# STM32F429.net
KiCad netlist of a schematic drawn in Altium Designer
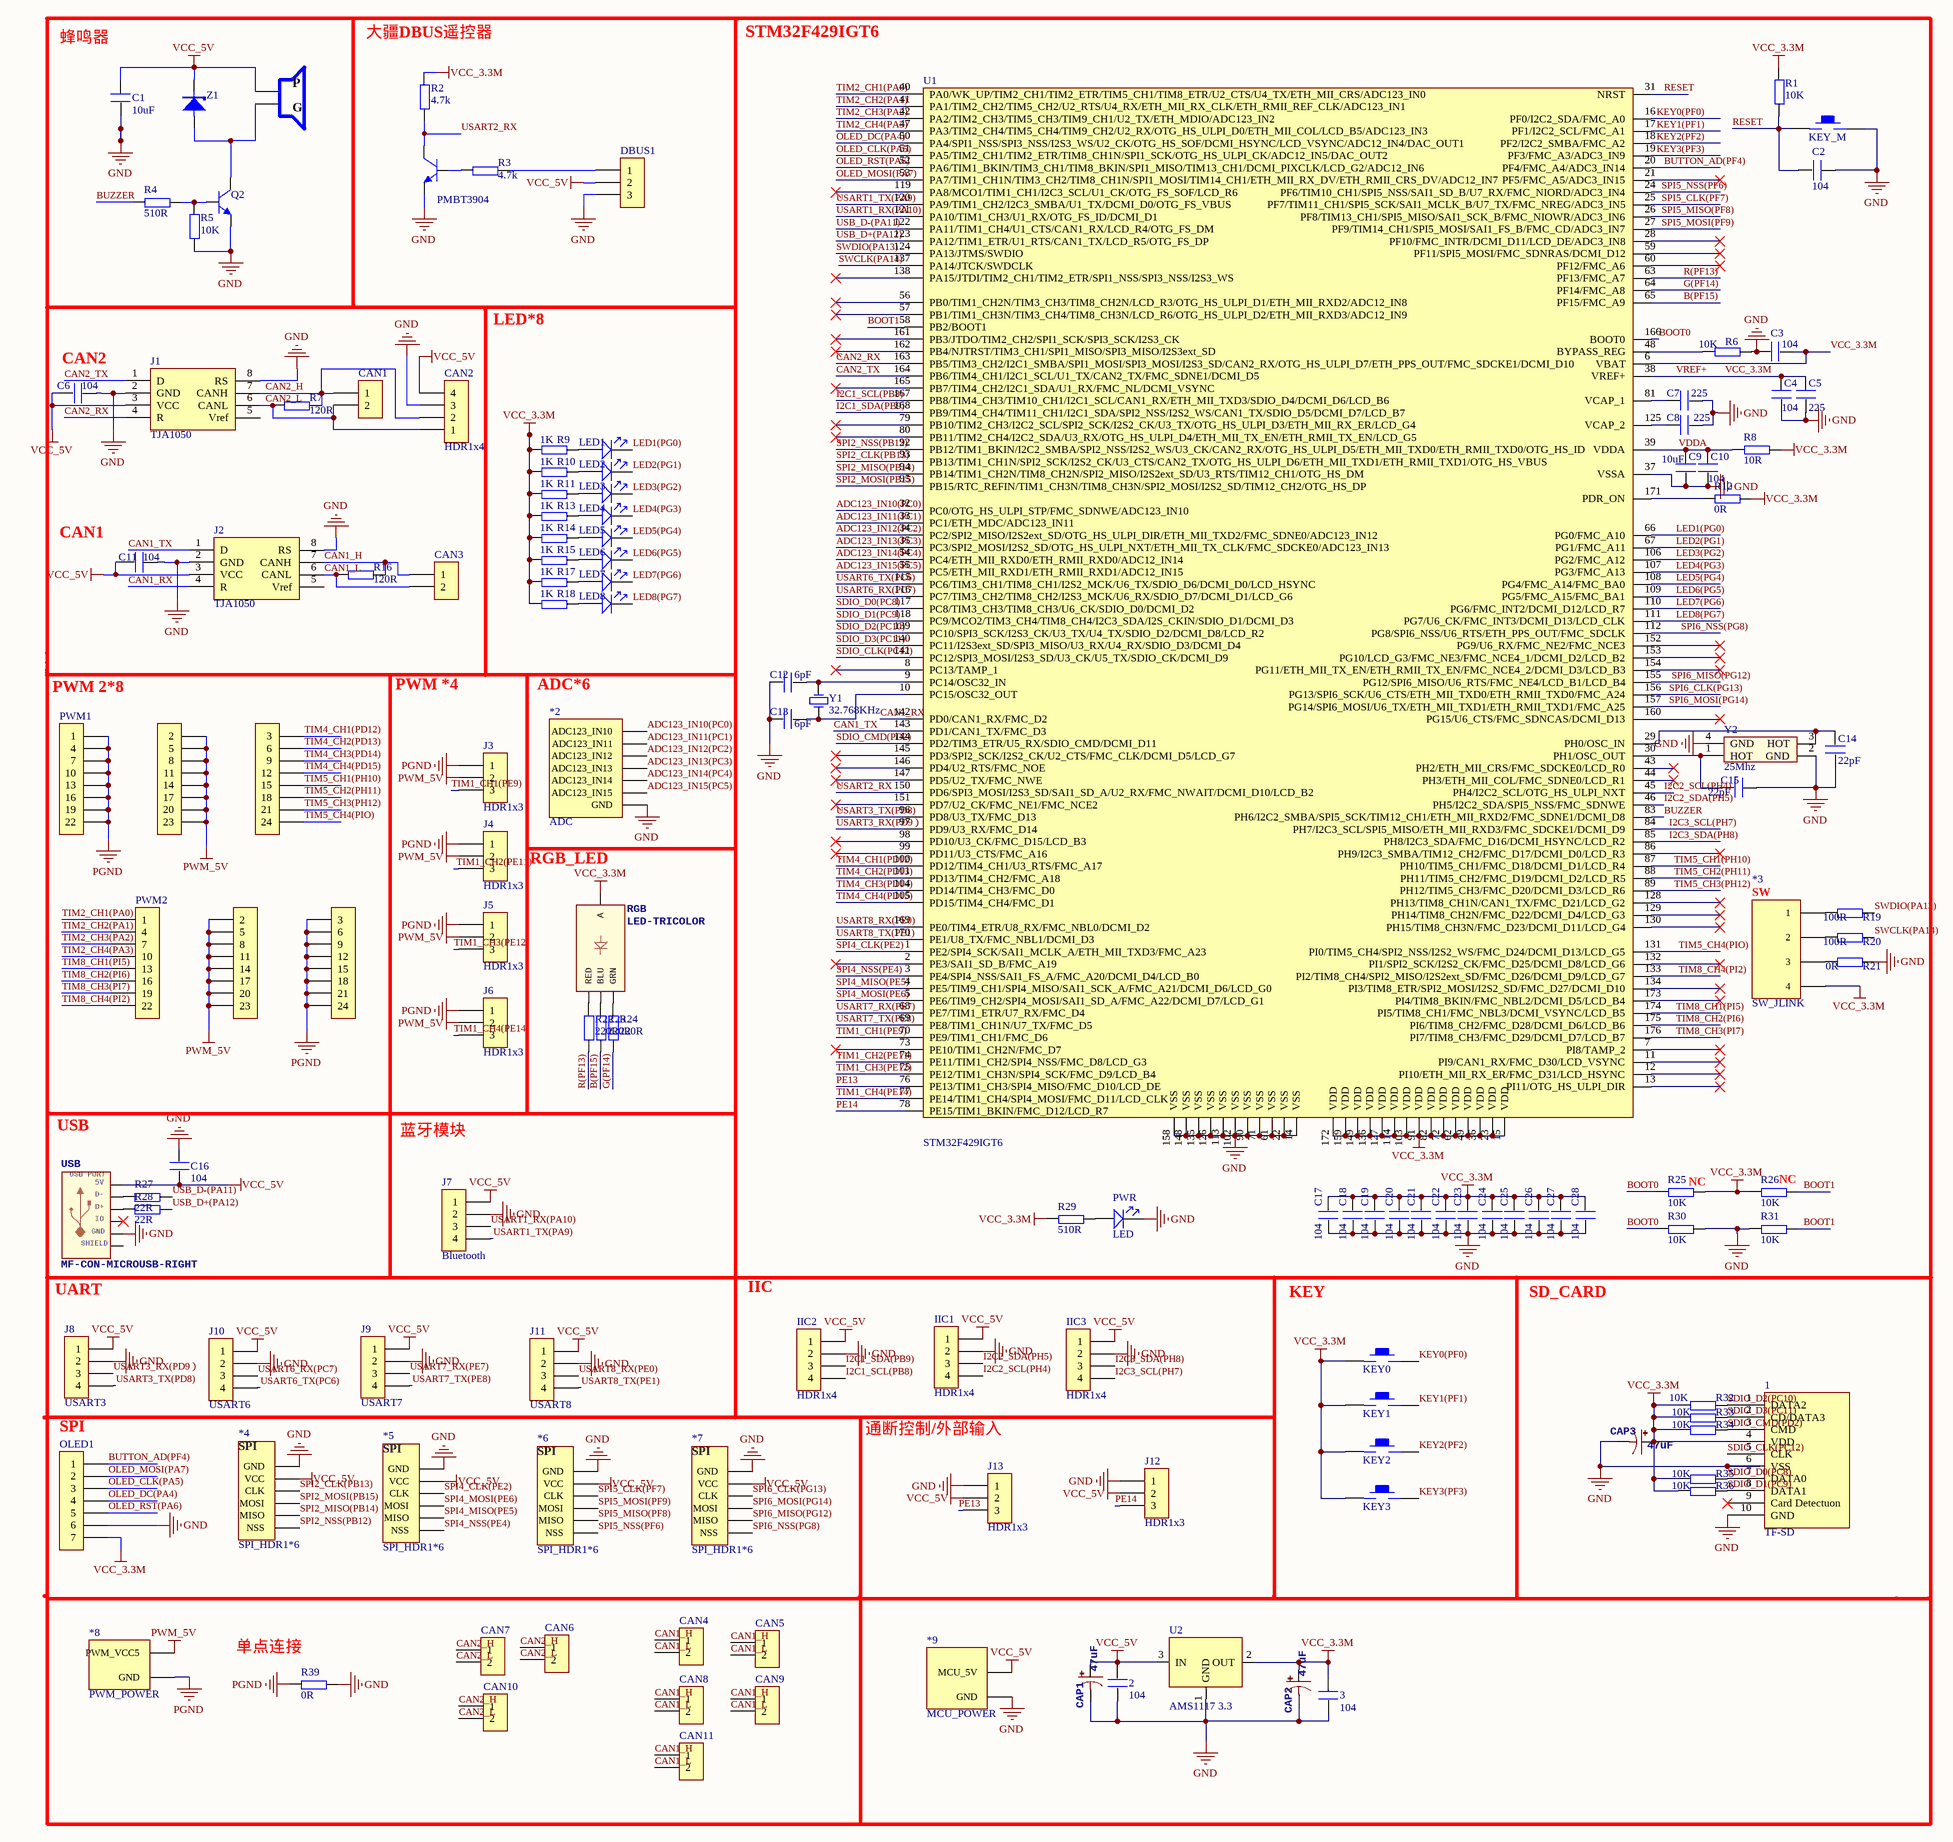
[diagram p0: STM32F429.SchDoc]

(export (version "E")
  (design (tool "Eeschema 10.0.6"))
  (components
    (comp (ref "*1")
      (value "BUZZER")
      (footprint "STM32F429_CORE1:BUZZER")
      (libsource (lib "转接板v2") (part "BUZZER"))
    )
    (comp (ref "*2")
      (value "ADC")
      (footprint "STM32F429_CORE1:ADC")
      (libsource (lib "STM32F429_CORE") (part "ADC"))
    )
    (comp (ref "*3")
      (value "SW_JLINK")
      (footprint "STM32F429_CORE1:GH1.25-立贴-4P")
      (libsource (lib "STM32F429_CORE") (part "SW_JLINK"))
    )
    (comp (ref "*4")
      (value "SPI_HDR1*6")
      (footprint "STM32F429_CORE1:GH1.25-立贴-6P")
      (libsource (lib "STM32F429_CORE") (part "SPI_HDR1*6"))
    )
    (comp (ref "*5")
      (value "SPI_HDR1*6")
      (footprint "STM32F429_CORE1:GH1.25-立贴-6P")
      (libsource (lib "STM32F429_CORE") (part "SPI_HDR1*6"))
    )
    (comp (ref "*6")
      (value "SPI_HDR1*6")
      (footprint "STM32F429_CORE1:GH1.25-立贴-6P")
      (libsource (lib "STM32F429_CORE") (part "SPI_HDR1*6"))
    )
    (comp (ref "*7")
      (value "SPI_HDR1*6")
      (footprint "STM32F429_CORE1:GH1.25-立贴-6P")
      (libsource (lib "STM32F429_CORE") (part "SPI_HDR1*6"))
    )
    (comp (ref "*8")
      (value "PWM_POWER")
      (footprint "XT30_PW母头")
      (libsource (lib "STM32F429_CORE") (part "PWM_POWER"))
    )
    (comp (ref "*9")
      (value "MCU_POWER")
      (footprint "STM32F429_CORE1:XT30_PW母头")
      (libsource (lib "STM32F429_CORE") (part "MCU_POWER"))
    )
    (comp (ref "1")
      (value "TF-SD")
      (footprint "STM32F429_CORE1:TF")
      (libsource (lib "STM32F429_CORE") (part "TF-SD"))
    )
    (comp (ref "2")
      (value "104")
      (footprint "STM32F429_CORE1:0603P")
      (libsource (lib "STM32F429_CORE") (part "C"))
    )
    (comp (ref "3")
      (value "104")
      (footprint "STM32F429_CORE1:0603P")
      (libsource (lib "STM32F429_CORE") (part "C"))
    )
    (comp (ref "C1")
      (value "10uF")
      (footprint "STM32F429_CORE1:0603P")
      (libsource (lib "STM32F429_CORE") (part "C"))
    )
    (comp (ref "C2") (value "104") (footprint "0603P") (libsource (lib "STM32F429_CORE") (part "C")))
    (comp (ref "C3") (value "104") (footprint "0603P") (libsource (lib "STM32F429_CORE") (part "C")))
    (comp (ref "C4") (value "104") (footprint "0603P") (libsource (lib "STM32F429_CORE") (part "C")))
    (comp (ref "C5") (value "225") (footprint "0603P") (libsource (lib "STM32F429_CORE") (part "C")))
    (comp (ref "C6")
      (value "104")
      (footprint "STM32F429_CORE1:0603P")
      (libsource (lib "STM32F429_CORE") (part "C"))
    )
    (comp (ref "C7") (value "225") (footprint "0603P") (libsource (lib "STM32F429_CORE") (part "C")))
    (comp (ref "C8") (value "225") (footprint "0603P") (libsource (lib "STM32F429_CORE") (part "C")))
    (comp (ref "C9") (value "10uF") (footprint "0603P") (libsource (lib "STM32F429_CORE") (part "C")))
    (comp (ref "C10") (value "104") (footprint "0603P") (libsource (lib "STM32F429_CORE") (part "C")))
    (comp (ref "C11")
      (value "104")
      (footprint "STM32F429_CORE1:0603P")
      (libsource (lib "STM32F429_CORE") (part "C"))
    )
    (comp (ref "C12") (value "6pF") (footprint "0603P") (libsource (lib "STM32F429_CORE") (part "C")))
    (comp (ref "C13") (value "6pF") (footprint "0603P") (libsource (lib "STM32F429_CORE") (part "C")))
    (comp (ref "C14") (value "22pF") (footprint "0603P") (libsource (lib "STM32F429_CORE") (part "C")))
    (comp (ref "C15") (value "22pF") (footprint "0603P") (libsource (lib "STM32F429_CORE") (part "C")))
    (comp (ref "C16") (value "104") (footprint "0603P") (libsource (lib "STM32F429_CORE") (part "C")))
    (comp (ref "C17") (value "104") (footprint "0603P") (libsource (lib "STM32F429_CORE") (part "C")))
    (comp (ref "C18") (value "104") (footprint "0603P") (libsource (lib "STM32F429_CORE") (part "C")))
    (comp (ref "C19") (value "104") (footprint "0603P") (libsource (lib "STM32F429_CORE") (part "C")))
    (comp (ref "C20") (value "104") (footprint "0603P") (libsource (lib "STM32F429_CORE") (part "C")))
    (comp (ref "C21") (value "104") (footprint "0603P") (libsource (lib "STM32F429_CORE") (part "C")))
    (comp (ref "C22") (value "104") (footprint "0603P") (libsource (lib "STM32F429_CORE") (part "C")))
    (comp (ref "C23") (value "104") (footprint "0603P") (libsource (lib "STM32F429_CORE") (part "C")))
    (comp (ref "C24") (value "104") (footprint "0603P") (libsource (lib "STM32F429_CORE") (part "C")))
    (comp (ref "C25") (value "104") (footprint "0603P") (libsource (lib "STM32F429_CORE") (part "C")))
    (comp (ref "C26") (value "104") (footprint "0603P") (libsource (lib "STM32F429_CORE") (part "C")))
    (comp (ref "C27") (value "104") (footprint "0603P") (libsource (lib "STM32F429_CORE") (part "C")))
    (comp (ref "C28") (value "104") (footprint "0603P") (libsource (lib "STM32F429_CORE") (part "C")))
    (comp (ref "CAN1")
      (value "HDR1x2-right")
      (footprint "STM32F429_CORE1:GH1.25-立贴-2P")
      (description "Connector")
      (libsource (lib "adaptor_plate") (part "HDR1x2-right"))
    )
    (comp (ref "CAN2")
      (value "HDR1x4")
      (footprint "STM32F429_CORE1:GH1.25-立贴-4P")
      (description "Connector")
      (libsource (lib "") (part "HDR1x4_1"))
    )
    (comp (ref "CAN3")
      (value "HDR1x2-right")
      (footprint "STM32F429_CORE1:GH1.25-立贴-2P")
      (description "Connector")
      (libsource (lib "adaptor_plate") (part "HDR1x2-right"))
    )
    (comp (ref "CAN4")
      (value "HDR1x2-right")
      (footprint "STM32F429_CORE1:GH1.25-立贴-2P")
      (description "Connector")
      (libsource (lib "adaptor_plate") (part "HDR1x2-right"))
    )
    (comp (ref "CAN5")
      (value "HDR1x2-right")
      (footprint "STM32F429_CORE1:GH1.25-立贴-2P")
      (description "Connector")
      (libsource (lib "adaptor_plate") (part "HDR1x2-right"))
    )
    (comp (ref "CAN6")
      (value "HDR1x2-right")
      (footprint "STM32F429_CORE1:GH1.25-立贴-2P")
      (description "Connector")
      (libsource (lib "adaptor_plate") (part "HDR1x2-right"))
    )
    (comp (ref "CAN7")
      (value "HDR1x2-right")
      (footprint "STM32F429_CORE1:GH1.25-立贴-2P")
      (description "Connector")
      (libsource (lib "adaptor_plate") (part "HDR1x2-right"))
    )
    (comp (ref "CAN8")
      (value "HDR1x2-right")
      (footprint "STM32F429_CORE1:GH1.25-立贴-2P")
      (description "Connector")
      (libsource (lib "adaptor_plate") (part "HDR1x2-right"))
    )
    (comp (ref "CAN9")
      (value "HDR1x2-right")
      (footprint "STM32F429_CORE1:GH1.25-立贴-2P")
      (description "Connector")
      (libsource (lib "adaptor_plate") (part "HDR1x2-right"))
    )
    (comp (ref "CAN10")
      (value "HDR1x2-right")
      (footprint "STM32F429_CORE1:GH1.25-立贴-2P")
      (description "Connector")
      (libsource (lib "adaptor_plate") (part "HDR1x2-right"))
    )
    (comp (ref "CAN11")
      (value "HDR1x2-right")
      (footprint "STM32F429_CORE1:GH1.25-立贴-2P")
      (description "Connector")
      (libsource (lib "adaptor_plate") (part "HDR1x2-right"))
    )
    (comp (ref "CAP1") (value "47uF") (footprint "EIA3216") (libsource (lib "") (part "CAP_POL1206_1")))
    (comp (ref "CAP2") (value "47uF") (footprint "EIA3216") (libsource (lib "") (part "CAP_POL1206_1")))
    (comp (ref "CAP3")
      (value "47uF")
      (footprint "EIA3216")
      (libsource (lib "STM32F429_CORE") (part "CAP_POL1206"))
    )
    (comp (ref "DBUS1")
      (value "HDR1x3-right")
      (footprint "STM32F429_CORE1:PIN-1*3-2.54")
      (description "Connector")
      (libsource (lib "adaptor_plate") (part "HDR1x3-right"))
    )
    (comp (ref "IIC1")
      (value "HDR1x4")
      (footprint "STM32F429_CORE1:GH1.25-立贴-4P")
      (description "Connector")
      (libsource (lib "STM32F429_CORE") (part "HDR1x4"))
    )
    (comp (ref "IIC2")
      (value "HDR1x4")
      (footprint "STM32F429_CORE1:GH1.25-立贴-4P")
      (description "Connector")
      (libsource (lib "STM32F429_CORE") (part "HDR1x4"))
    )
    (comp (ref "IIC3")
      (value "HDR1x4")
      (footprint "STM32F429_CORE1:GH1.25-立贴-4P")
      (description "Connector")
      (libsource (lib "STM32F429_CORE") (part "HDR1x4"))
    )
    (comp (ref "J1")
      (value "TJA1050")
      (footprint "SOIC-8_150mil")
      (description "CAN芯片")
      (libsource (lib "adaptor_plate") (part "TJA1050"))
    )
    (comp (ref "J2")
      (value "TJA1050")
      (footprint "SOIC-8_150mil")
      (description "CAN芯片")
      (libsource (lib "adaptor_plate") (part "TJA1050"))
    )
    (comp (ref "J3")
      (value "HDR1x3")
      (footprint "STM32F429_CORE1:HDR1X3")
      (description "Connector")
      (libsource (lib "STM32F429_CORE") (part "HDR1x3"))
    )
    (comp (ref "J4")
      (value "HDR1x3")
      (footprint "STM32F429_CORE1:HDR1X3")
      (description "Connector")
      (libsource (lib "STM32F429_CORE") (part "HDR1x3"))
    )
    (comp (ref "J5")
      (value "HDR1x3")
      (footprint "STM32F429_CORE1:HDR1X3")
      (description "Connector")
      (libsource (lib "STM32F429_CORE") (part "HDR1x3"))
    )
    (comp (ref "J6")
      (value "HDR1x3")
      (footprint "STM32F429_CORE1:HDR1X3")
      (description "Connector")
      (libsource (lib "STM32F429_CORE") (part "HDR1x3"))
    )
    (comp (ref "J7")
      (value "Bluetooth")
      (footprint "STM32F429_CORE1:1X04")
      (description "Connector")
      (libsource (lib "STM32F429_CORE") (part "HDR1x4"))
    )
    (comp (ref "J8")
      (value "USART3")
      (footprint "STM32F429_CORE1:GH1.25-立贴-4P")
      (description "Connector")
      (libsource (lib "STM32F429_CORE") (part "HDR1x4"))
    )
    (comp (ref "J9")
      (value "USART7")
      (footprint "STM32F429_CORE1:GH1.25-立贴-4P")
      (description "Connector")
      (libsource (lib "STM32F429_CORE") (part "HDR1x4"))
    )
    (comp (ref "J10")
      (value "USART6")
      (footprint "STM32F429_CORE1:GH1.25-立贴-4P")
      (description "Connector")
      (libsource (lib "STM32F429_CORE") (part "HDR1x4"))
    )
    (comp (ref "J11")
      (value "USART8")
      (footprint "STM32F429_CORE1:GH1.25-立贴-4P")
      (description "Connector")
      (libsource (lib "STM32F429_CORE") (part "HDR1x4"))
    )
    (comp (ref "J12")
      (value "HDR1x3")
      (footprint "STM32F429_CORE1:HDR1X3")
      (description "Connector")
      (libsource (lib "STM32F429_CORE") (part "HDR1x3"))
    )
    (comp (ref "J13")
      (value "HDR1x3")
      (footprint "STM32F429_CORE1:HDR1X3")
      (description "Connector")
      (libsource (lib "STM32F429_CORE") (part "HDR1x3"))
    )
    (comp (ref "KEY1")
      (value "KEY0")
      (footprint "STM32F429_CORE1:KEY_SOP324225")
      (libsource (lib "STM32F429_CORE") (part "KEY_M"))
    )
    (comp (ref "KEY2")
      (value "KEY1")
      (footprint "STM32F429_CORE1:KEY_SOP324225")
      (libsource (lib "STM32F429_CORE") (part "KEY_M"))
    )
    (comp (ref "KEY3")
      (value "KEY2")
      (footprint "STM32F429_CORE1:KEY_SOP324225")
      (libsource (lib "STM32F429_CORE") (part "KEY_M"))
    )
    (comp (ref "KEY4")
      (value "KEY3")
      (footprint "STM32F429_CORE1:KEY_SOP324225")
      (libsource (lib "STM32F429_CORE") (part "KEY_M"))
    )
    (comp (ref "LED1")
      (value "LED")
      (footprint "STM32F429_CORE1:0805 LED")
      (libsource (lib "STM32F429_CORE") (part "LED"))
    )
    (comp (ref "LED2")
      (value "LED")
      (footprint "STM32F429_CORE1:0805 LED")
      (libsource (lib "STM32F429_CORE") (part "LED"))
    )
    (comp (ref "LED3")
      (value "LED")
      (footprint "STM32F429_CORE1:0805 LED")
      (libsource (lib "STM32F429_CORE") (part "LED"))
    )
    (comp (ref "LED4")
      (value "LED")
      (footprint "STM32F429_CORE1:0805 LED")
      (libsource (lib "STM32F429_CORE") (part "LED"))
    )
    (comp (ref "LED5")
      (value "LED")
      (footprint "STM32F429_CORE1:0805 LED")
      (libsource (lib "STM32F429_CORE") (part "LED"))
    )
    (comp (ref "LED6")
      (value "LED")
      (footprint "STM32F429_CORE1:0805 LED")
      (libsource (lib "STM32F429_CORE") (part "LED"))
    )
    (comp (ref "LED7")
      (value "LED")
      (footprint "STM32F429_CORE1:0805 LED")
      (libsource (lib "STM32F429_CORE") (part "LED"))
    )
    (comp (ref "LED8")
      (value "LED")
      (footprint "STM32F429_CORE1:0805 LED")
      (libsource (lib "STM32F429_CORE") (part "LED"))
    )
    (comp (ref "OLED1")
      (value "HDR1x7-left")
      (footprint "STM32F429_CORE1:GH1.25-立贴-7P")
      (description "Connector")
      (libsource (lib "adaptor_plate") (part "HDR1x7-left"))
    )
    (comp (ref "PWM1")
      (value "HDR3*8-right")
      (footprint "STM32F429_CORE1:PIN-3*8-2.54 - duplicate")
      (description "Connector")
      (libsource (lib "adaptor_plate") (part "HDR3*8-right"))
    )
    (comp (ref "PWM2")
      (value "HDR3*8-left")
      (footprint "STM32F429_CORE1:PIN-3*8-2.54 - duplicate")
      (description "Connector")
      (libsource (lib "adaptor_plate") (part "HDR3*8-left"))
    )
    (comp (ref "PWR")
      (value "LED")
      (footprint "STM32F429_CORE1:0805 LED")
      (libsource (lib "STM32F429_CORE") (part "LED"))
    )
    (comp (ref "Q1")
      (value "PMBT3904")
      (footprint "SOT-23-3")
      (description "NPN Bipolar Transistor")
      (libsource (lib "adaptor_plate") (part "PMBT3904"))
    )
    (comp (ref "Q2")
      (value "S8050")
      (footprint "STM32F429_CORE1:SOT-23-3")
      (description "NPN Bipolar Transistor")
      (libsource (lib "转接板v2") (part "BJT"))
    )
    (comp (ref "R1") (value "10K") (footprint "0603P") (libsource (lib "STM32F429_CORE") (part "R")))
    (comp (ref "R2")
      (value "4.7k")
      (footprint "STM32F429_CORE1:0603P")
      (description "Resistance")
      (libsource (lib "adaptor_plate") (part "RES"))
    )
    (comp (ref "R3")
      (value "4.7k")
      (footprint "STM32F429_CORE1:0603P")
      (description "Resistance")
      (libsource (lib "adaptor_plate") (part "RES"))
    )
    (comp (ref "R4")
      (value "510R")
      (footprint "STM32F429_CORE1:0603P")
      (description "Resistance")
      (libsource (lib "转接板v2") (part "RES"))
    )
    (comp (ref "R5")
      (value "10K")
      (footprint "STM32F429_CORE1:0603P")
      (description "Resistance")
      (libsource (lib "转接板v2") (part "RES"))
    )
    (comp (ref "R6") (value "10K") (footprint "0603P") (libsource (lib "STM32F429_CORE") (part "R")))
    (comp (ref "R7")
      (value "120R")
      (footprint "STM32F429_CORE1:0603P")
      (description "Resistance")
      (libsource (lib "adaptor_plate") (part "RES"))
    )
    (comp (ref "R8") (value "10R") (footprint "0603P") (libsource (lib "STM32F429_CORE") (part "R")))
    (comp (ref "R9") (value "1K") (footprint "0603P") (libsource (lib "STM32F429_CORE") (part "R")))
    (comp (ref "R10") (value "1K") (footprint "0603P") (libsource (lib "STM32F429_CORE") (part "R")))
    (comp (ref "R11") (value "1K") (footprint "0603P") (libsource (lib "STM32F429_CORE") (part "R")))
    (comp (ref "R12") (value "0R") (footprint "0603P") (libsource (lib "STM32F429_CORE") (part "R")))
    (comp (ref "R13") (value "1K") (footprint "0603P") (libsource (lib "STM32F429_CORE") (part "R")))
    (comp (ref "R14") (value "1K") (footprint "0603P") (libsource (lib "STM32F429_CORE") (part "R")))
    (comp (ref "R15") (value "1K") (footprint "0603P") (libsource (lib "STM32F429_CORE") (part "R")))
    (comp (ref "R16")
      (value "120R")
      (footprint "STM32F429_CORE1:0603P")
      (description "Resistance")
      (libsource (lib "adaptor_plate") (part "RES"))
    )
    (comp (ref "R17") (value "1K") (footprint "0603P") (libsource (lib "STM32F429_CORE") (part "R")))
    (comp (ref "R18") (value "1K") (footprint "0603P") (libsource (lib "STM32F429_CORE") (part "R")))
    (comp (ref "R19") (value "100R") (footprint "0603P") (libsource (lib "STM32F429_CORE") (part "R")))
    (comp (ref "R20") (value "100R") (footprint "0603P") (libsource (lib "STM32F429_CORE") (part "R")))
    (comp (ref "R21") (value "0R") (footprint "0603P") (libsource (lib "STM32F429_CORE") (part "R")))
    (comp (ref "R22") (value "220R") (footprint "0603P") (libsource (lib "STM32F429_CORE") (part "R")))
    (comp (ref "R23") (value "220R") (footprint "0603P") (libsource (lib "STM32F429_CORE") (part "R")))
    (comp (ref "R24") (value "220R") (footprint "0603P") (libsource (lib "STM32F429_CORE") (part "R")))
    (comp (ref "R25") (value "10K") (footprint "0603P") (libsource (lib "STM32F429_CORE") (part "R")))
    (comp (ref "R26") (value "10K") (footprint "0603P") (libsource (lib "STM32F429_CORE") (part "R")))
    (comp (ref "R27") (value "22R") (footprint "0603P") (libsource (lib "STM32F429_CORE") (part "R")))
    (comp (ref "R28") (value "22R") (footprint "0603P") (libsource (lib "STM32F429_CORE") (part "R")))
    (comp (ref "R29") (value "510R") (footprint "0603P") (libsource (lib "STM32F429_CORE") (part "R")))
    (comp (ref "R30") (value "10K") (footprint "0603P") (libsource (lib "STM32F429_CORE") (part "R")))
    (comp (ref "R31") (value "10K") (footprint "0603P") (libsource (lib "STM32F429_CORE") (part "R")))
    (comp (ref "R32") (value "10K") (footprint "0603P") (libsource (lib "STM32F429_CORE") (part "R")))
    (comp (ref "R33") (value "10K") (footprint "0603P") (libsource (lib "STM32F429_CORE") (part "R")))
    (comp (ref "R34") (value "10K") (footprint "0603P") (libsource (lib "STM32F429_CORE") (part "R")))
    (comp (ref "R35") (value "10K") (footprint "0603P") (libsource (lib "STM32F429_CORE") (part "R")))
    (comp (ref "R36") (value "10K") (footprint "0603P") (libsource (lib "STM32F429_CORE") (part "R")))
    (comp (ref "R39") (value "0R") (footprint "0805") (libsource (lib "STM32F429_CORE") (part "R")))
    (comp (ref "RGB")
      (value "LED-TRICOLOR")
      (footprint "rgb")
      (libsource (lib "STM32F429_CORE") (part "LED-TRICOLOR"))
    )
    (comp (ref "RST1")
      (value "KEY_M")
      (footprint "STM32F429_CORE1:KEY_SOP324225")
      (libsource (lib "STM32F429_CORE") (part "KEY_M"))
    )
    (comp (ref "U1")
      (value "STM32F429IGT6")
      (footprint "LQFP176")
      (libsource (lib "STM32F429_CORE") (part "STM32F429IGT6"))
    )
    (comp (ref "U2")
      (value "AMS1117 3.3")
      (footprint "SOT_223")
      (libsource (lib "STM32F429_CORE") (part "AMS1117"))
    )
    (comp (ref "USB")
      (value "MF-CON-MICROUSB-RIGHT")
      (footprint "STM32F429_CORE1:micro_usb")
      (fields
        (field (name "USBPORT") "USB PORT")
        (field (name "5V") "5V")
        (field (name "D-") "D-")
        (field (name "D+") "D+")
        (field (name "ID") "ID")
        (field (name "GND") "GND")
        (field (name "SHIELD") "SHIELD")
      )
      (libsource (lib "STM32F429_CORE") (part "USB_MICRO_RIGHT"))
    )
    (comp (ref "Y1")
      (value "32.768KHz")
      (footprint "STM32F429_CORE1:XTAL3215")
      (description "普通晶振")
      (fields (field (name "PUBLISHER") "Altium Limited"))
      (libsource (lib "STM32F429_CORE") (part "XTAL"))
    )
    (comp (ref "Y2")
      (value "25Mhz")
      (footprint "XTAL3225")
      (description "3225贴片无源晶振")
      (libsource (lib "STM32F429_CORE") (part "XTAL_3225"))
    )
    (comp (ref "Z1")
      (value "MMSZ4684")
      (footprint "STM32F429_CORE1:SOD-123")
      (description "Zener Diode")
      (libsource (lib "转接板v2") (part "Diode"))
    )
  )
  (nets
    (net (code "1") (name "/ADC123_IN10(PC0)") (class "Default")
      (node (ref "*2") (pin "0") (pinfunction "ADC123_IN10_0") (pintype "passive"))
      (node (ref "U1") (pin "32") (pinfunction "PC0/OTG_HS_ULPI_STP/FMC_SDNWE/ADC123_IN10_32") (pintype "passive"))
    )
    (net (code "2") (name "/ADC123_IN11(PC1)") (class "Default")
      (node (ref "*2") (pin "1") (pinfunction "ADC123_IN11_1") (pintype "passive"))
      (node (ref "U1") (pin "33") (pinfunction "PC1/ETH_MDC/ADC123_IN11_33") (pintype "passive"))
    )
    (net (code "3") (name "/ADC123_IN12(PC2)") (class "Default")
      (node (ref "*2") (pin "2") (pinfunction "ADC123_IN12_2") (pintype "passive"))
      (node (ref "U1") (pin "34") (pinfunction "PC2/SPI2_MISO/I2S2ext_SD/OTG_HS_ULPI_DIR/ETH_MII_TXD2/FMC_SDNE0/ADC123_IN12_34") (pintype "passive"))
    )
    (net (code "4") (name "/ADC123_IN13(PC3)") (class "Default")
      (node (ref "*2") (pin "3") (pinfunction "ADC123_IN13_3") (pintype "passive"))
      (node (ref "U1") (pin "35") (pinfunction "PC3/SPI2_MOSI/I2S2_SD/OTG_HS_ULPI_NXT/ETH_MII_TX_CLK/FMC_SDCKE0/ADC123_IN13_35") (pintype "passive"))
    )
    (net (code "5") (name "/ADC123_IN14(PC4)") (class "Default")
      (node (ref "*2") (pin "4") (pinfunction "ADC123_IN14_4") (pintype "passive"))
      (node (ref "U1") (pin "54") (pinfunction "PC4/ETH_MII_RXD0/ETH_RMII_RXD0/ADC12_IN14_54") (pintype "passive"))
    )
    (net (code "6") (name "/ADC123_IN15(PC5)") (class "Default")
      (node (ref "*2") (pin "5") (pinfunction "ADC123_IN15_5") (pintype "passive"))
      (node (ref "U1") (pin "55") (pinfunction "PC5/ETH_MII_RXD1/ETH_RMII_RXD1/ADC12_IN15_55") (pintype "passive"))
    )
    (net (code "7") (name "/B(PF15)") (class "Default")
      (node (ref "R23") (pin "1") (pintype "passive"))
      (node (ref "U1") (pin "65") (pinfunction "PF15/FMC_A9_65") (pintype "passive"))
    )
    (net (code "8") (name "/BOOT0") (class "Default")
      (node (ref "R25") (pin "1") (pintype "passive"))
      (node (ref "R30") (pin "1") (pintype "passive"))
      (node (ref "U1") (pin "166") (pinfunction "BOOT0_166") (pintype "passive"))
    )
    (net (code "9") (name "/BOOT1") (class "Default")
      (node (ref "R26") (pin "2") (pintype "passive"))
      (node (ref "R31") (pin "2") (pintype "passive"))
      (node (ref "U1") (pin "58") (pinfunction "PB2/BOOT1_58") (pintype "passive"))
    )
    (net (code "10") (name "/BUTTON_AD(PF4)") (class "Default")
      (node (ref "OLED1") (pin "1") (pinfunction "1_1") (pintype "passive"))
      (node (ref "U1") (pin "20") (pinfunction "PF4/FMC_A4/ADC3_IN14_20") (pintype "passive"))
    )
    (net (code "11") (name "/BUZZER") (class "Default")
      (node (ref "R4") (pin "1") (pintype "passive"))
      (node (ref "U1") (pin "83") (pinfunction "PH6/I2C2_SMBA/SPI5_SCK/TIM12_CH1/ETH_MII_RXD2/FMC_SDNE1/DCMI_D8_83") (pintype "passive"))
    )
    (net (code "12") (name "/CAN1_H") (class "Default")
      (node (ref "CAN11") (pin "1") (pinfunction "1_1") (pintype "passive"))
      (node (ref "CAN3") (pin "1") (pinfunction "1_1") (pintype "passive"))
      (node (ref "CAN4") (pin "1") (pinfunction "1_1") (pintype "passive"))
      (node (ref "CAN5") (pin "1") (pinfunction "1_1") (pintype "passive"))
      (node (ref "CAN8") (pin "1") (pinfunction "1_1") (pintype "passive"))
      (node (ref "CAN9") (pin "1") (pinfunction "1_1") (pintype "passive"))
      (node (ref "J2") (pin "7") (pinfunction "CANH_7") (pintype "passive"))
      (node (ref "R16") (pin "2") (pintype "passive"))
    )
    (net (code "13") (name "/CAN1_L") (class "Default")
      (node (ref "CAN11") (pin "2") (pinfunction "2_2") (pintype "passive"))
      (node (ref "CAN3") (pin "2") (pinfunction "2_2") (pintype "passive"))
      (node (ref "CAN4") (pin "2") (pinfunction "2_2") (pintype "passive"))
      (node (ref "CAN5") (pin "2") (pinfunction "2_2") (pintype "passive"))
      (node (ref "CAN8") (pin "2") (pinfunction "2_2") (pintype "passive"))
      (node (ref "CAN9") (pin "2") (pinfunction "2_2") (pintype "passive"))
      (node (ref "J2") (pin "6") (pinfunction "CANL_6") (pintype "passive"))
      (node (ref "R16") (pin "1") (pintype "passive"))
    )
    (net (code "14") (name "/CAN1_RX") (class "Default")
      (node (ref "J2") (pin "4") (pinfunction "R_4") (pintype "passive"))
      (node (ref "U1") (pin "142") (pinfunction "PD0/CAN1_RX/FMC_D2_142") (pintype "passive"))
    )
    (net (code "15") (name "/CAN1_TX") (class "Default")
      (node (ref "J2") (pin "1") (pinfunction "D_1") (pintype "passive"))
      (node (ref "U1") (pin "143") (pinfunction "PD1/CAN1_TX/FMC_D3_143") (pintype "passive"))
    )
    (net (code "16") (name "/CAN2_H") (class "Default")
      (node (ref "CAN1") (pin "1") (pinfunction "1_1") (pintype "passive"))
      (node (ref "CAN10") (pin "1") (pinfunction "1_1") (pintype "passive"))
      (node (ref "CAN2") (pin "2") (pinfunction "2_2") (pintype "passive"))
      (node (ref "CAN6") (pin "1") (pinfunction "1_1") (pintype "passive"))
      (node (ref "CAN7") (pin "1") (pinfunction "1_1") (pintype "passive"))
      (node (ref "J1") (pin "7") (pinfunction "CANH_7") (pintype "passive"))
      (node (ref "R7") (pin "2") (pintype "passive"))
    )
    (net (code "17") (name "/CAN2_L") (class "Default")
      (node (ref "CAN1") (pin "2") (pinfunction "2_2") (pintype "passive"))
      (node (ref "CAN10") (pin "2") (pinfunction "2_2") (pintype "passive"))
      (node (ref "CAN2") (pin "1") (pinfunction "1_1") (pintype "passive"))
      (node (ref "CAN6") (pin "2") (pinfunction "2_2") (pintype "passive"))
      (node (ref "CAN7") (pin "2") (pinfunction "2_2") (pintype "passive"))
      (node (ref "J1") (pin "6") (pinfunction "CANL_6") (pintype "passive"))
      (node (ref "R7") (pin "1") (pintype "passive"))
    )
    (net (code "18") (name "/CAN2_RX") (class "Default")
      (node (ref "J1") (pin "4") (pinfunction "R_4") (pintype "passive"))
      (node (ref "U1") (pin "163") (pinfunction "PB5/TIM3_CH2/I2C1_SMBA/SPI1_MOSI/SPI3_MOSI/I2S3_SD/CAN2_RX/OTG_HS_ULPI_D7/ETH_PPS_OUT/FMC_SDCKE1/DCMI_D10_163") (pintype "passive"))
    )
    (net (code "19") (name "/CAN2_TX") (class "Default")
      (node (ref "J1") (pin "1") (pinfunction "D_1") (pintype "passive"))
      (node (ref "U1") (pin "164") (pinfunction "PB6/TIM4_CH1/I2C1_SCL/U1_TX/CAN2_TX/FMC_SDNE1/DCMI_D5_164") (pintype "passive"))
    )
    (net (code "20") (name "/G(PF14)") (class "Default")
      (node (ref "R24") (pin "1") (pintype "passive"))
      (node (ref "U1") (pin "64") (pinfunction "PF14/FMC_A8_64") (pintype "passive"))
    )
    (net (code "21") (name "/I2C1_SCL(PB8)") (class "Default")
      (node (ref "IIC2") (pin "4") (pinfunction "4_4") (pintype "passive"))
      (node (ref "U1") (pin "167") (pinfunction "PB8/TIM4_CH3/TIM10_CH1/I2C1_SCL/CAN1_RX/ETH_MII_TXD3/SDIO_D4/DCMI_D6/LCD_B6_167") (pintype "passive"))
    )
    (net (code "22") (name "/I2C1_SDA(PB9)") (class "Default")
      (node (ref "IIC2") (pin "3") (pinfunction "3_3") (pintype "passive"))
      (node (ref "U1") (pin "168") (pinfunction "PB9/TIM4_CH4/TIM11_CH1/I2C1_SDA/SPI2_NSS/I2S2_WS/CAN1_TX/SDIO_D5/DCMI_D7/LCD_B7_168") (pintype "passive"))
    )
    (net (code "23") (name "/I2C2_SCL(PH4)") (class "Default")
      (node (ref "IIC1") (pin "4") (pinfunction "4_4") (pintype "passive"))
      (node (ref "U1") (pin "45") (pinfunction "PH4/I2C2_SCL/OTG_HS_ULPI_NXT_45") (pintype "passive"))
    )
    (net (code "24") (name "/I2C2_SDA(PH5)") (class "Default")
      (node (ref "IIC1") (pin "3") (pinfunction "3_3") (pintype "passive"))
      (node (ref "U1") (pin "46") (pinfunction "PH5/I2C2_SDA/SPI5_NSS/FMC_SDNWE_46") (pintype "passive"))
    )
    (net (code "25") (name "/I2C3_SCL(PH7)") (class "Default")
      (node (ref "IIC3") (pin "4") (pinfunction "4_4") (pintype "passive"))
      (node (ref "U1") (pin "84") (pinfunction "PH7/I2C3_SCL/SPI5_MISO/ETH_MII_RXD3/FMC_SDCKE1/DCMI_D9_84") (pintype "passive"))
    )
    (net (code "26") (name "/I2C3_SDA(PH8)") (class "Default")
      (node (ref "IIC3") (pin "3") (pinfunction "3_3") (pintype "passive"))
      (node (ref "U1") (pin "85") (pinfunction "PH8/I2C3_SDA/FMC_D16/DCMI_HSYNC/LCD_R2_85") (pintype "passive"))
    )
    (net (code "27") (name "/KEY0(PF0)") (class "Default")
      (node (ref "KEY1") (pin "2") (pinfunction "2_2") (pintype "passive"))
      (node (ref "U1") (pin "16") (pinfunction "PF0/I2C2_SDA/FMC_A0_16") (pintype "passive"))
    )
    (net (code "28") (name "/KEY1(PF1)") (class "Default")
      (node (ref "KEY2") (pin "2") (pinfunction "2_2") (pintype "passive"))
      (node (ref "U1") (pin "17") (pinfunction "PF1/I2C2_SCL/FMC_A1_17") (pintype "passive"))
    )
    (net (code "29") (name "/KEY2(PF2)") (class "Default")
      (node (ref "KEY3") (pin "2") (pinfunction "2_2") (pintype "passive"))
      (node (ref "U1") (pin "18") (pinfunction "PF2/I2C2_SMBA/FMC_A2_18") (pintype "passive"))
    )
    (net (code "30") (name "/KEY3(PF3)") (class "Default")
      (node (ref "KEY4") (pin "2") (pinfunction "2_2") (pintype "passive"))
      (node (ref "U1") (pin "19") (pinfunction "PF3/FMC_A3/ADC3_IN9_19") (pintype "passive"))
    )
    (net (code "31") (name "/LED1(PG0)") (class "Default")
      (node (ref "LED1") (pin "2") (pinfunction "2_2") (pintype "passive"))
      (node (ref "U1") (pin "66") (pinfunction "PG0/FMC_A10_66") (pintype "passive"))
    )
    (net (code "32") (name "/LED2(PG1)") (class "Default")
      (node (ref "LED2") (pin "2") (pinfunction "2_2") (pintype "passive"))
      (node (ref "U1") (pin "67") (pinfunction "PG1/FMC_A11_67") (pintype "passive"))
    )
    (net (code "33") (name "/LED3(PG2)") (class "Default")
      (node (ref "LED3") (pin "2") (pinfunction "2_2") (pintype "passive"))
      (node (ref "U1") (pin "106") (pinfunction "PG2/FMC_A12_106") (pintype "passive"))
    )
    (net (code "34") (name "/LED4(PG3)") (class "Default")
      (node (ref "LED4") (pin "2") (pinfunction "2_2") (pintype "passive"))
      (node (ref "U1") (pin "107") (pinfunction "PG3/FMC_A13_107") (pintype "passive"))
    )
    (net (code "35") (name "/LED5(PG4)") (class "Default")
      (node (ref "LED5") (pin "2") (pinfunction "2_2") (pintype "passive"))
      (node (ref "U1") (pin "108") (pinfunction "PG4/FMC_A14/FMC_BA0_108") (pintype "passive"))
    )
    (net (code "36") (name "/LED6(PG5)") (class "Default")
      (node (ref "LED6") (pin "2") (pinfunction "2_2") (pintype "passive"))
      (node (ref "U1") (pin "109") (pinfunction "PG5/FMC_A15/FMC_BA1_109") (pintype "passive"))
    )
    (net (code "37") (name "/LED7(PG6)") (class "Default")
      (node (ref "LED7") (pin "2") (pinfunction "2_2") (pintype "passive"))
      (node (ref "U1") (pin "110") (pinfunction "PG6/FMC_INT2/DCMI_D12/LCD_R7_110") (pintype "passive"))
    )
    (net (code "38") (name "/LED8(PG7)") (class "Default")
      (node (ref "LED8") (pin "2") (pinfunction "2_2") (pintype "passive"))
      (node (ref "U1") (pin "111") (pinfunction "PG7/U6_CK/FMC_INT3/DCMI_D13/LCD_CLK_111") (pintype "passive"))
    )
    (net (code "39") (name "/OLED_CLK(PA5)") (class "Default")
      (node (ref "OLED1") (pin "3") (pinfunction "3_3") (pintype "passive"))
      (node (ref "U1") (pin "51") (pinfunction "PA5/TIM2_CH1/TIM2_ETR/TIM8_CH1N/SPI1_SCK/OTG_HS_ULPI_CK/ADC12_IN5/DAC_OUT2_51") (pintype "passive"))
    )
    (net (code "40") (name "/OLED_DC(PA4)") (class "Default")
      (node (ref "OLED1") (pin "4") (pinfunction "4_4") (pintype "passive"))
      (node (ref "U1") (pin "50") (pinfunction "PA4/SPI1_NSS/SPI3_NSS/I2S3_WS/U2_CK/OTG_HS_SOF/DCMI_HSYNC/LCD_VSYNC/ADC12_IN4/DAC_OUT1_50") (pintype "passive"))
    )
    (net (code "41") (name "/OLED_MOSI(PA7)") (class "Default")
      (node (ref "OLED1") (pin "2") (pinfunction "2_2") (pintype "passive"))
      (node (ref "U1") (pin "53") (pinfunction "PA7/TIM1_CH1N/TIM3_CH2/TIM8_CH1N/SPI1_MOSI/TIM14_CH1/ETH_MII_RX_DV/ETH_RMII_CRS_DV/ADC12_IN7_53") (pintype "passive"))
    )
    (net (code "42") (name "/OLED_RST(PA6)") (class "Default")
      (node (ref "OLED1") (pin "5") (pinfunction "5_5") (pintype "passive"))
      (node (ref "U1") (pin "52") (pinfunction "PA6/TIM1_BKIN/TIM3_CH1/TIM8_BKIN/SPI1_MISO/TIM13_CH1/DCMI_PIXCLK/LCD_G2/ADC12_IN6_52") (pintype "passive"))
    )
    (net (code "43") (name "/PE13") (class "Default")
      (node (ref "J13") (pin "3") (pinfunction "3_3") (pintype "passive"))
      (node (ref "U1") (pin "76") (pinfunction "PE13/TIM1_CH3/SPI4_MISO/FMC_D10/LCD_DE_76") (pintype "passive"))
    )
    (net (code "44") (name "/PE14") (class "Default")
      (node (ref "J12") (pin "3") (pinfunction "3_3") (pintype "passive"))
      (node (ref "U1") (pin "78") (pinfunction "PE15/TIM1_BKIN/FMC_D12/LCD_R7_78") (pintype "passive"))
    )
    (net (code "45") (name "/R(PF13)") (class "Default")
      (node (ref "R22") (pin "1") (pintype "passive"))
      (node (ref "U1") (pin "63") (pinfunction "PF13/FMC_A7_63") (pintype "passive"))
    )
    (net (code "46") (name "/RESET") (class "Default")
      (node (ref "C2") (pin "2") (pintype "passive"))
      (node (ref "R1") (pin "1") (pintype "passive"))
      (node (ref "RST1") (pin "1") (pinfunction "1_1") (pintype "passive"))
      (node (ref "U1") (pin "31") (pinfunction "NRST_31") (pintype "passive"))
    )
    (net (code "47") (name "/SDIO_CLK(PC12)") (class "Default")
      (node (ref "1") (pin "5") (pinfunction "CLK_5") (pintype "passive"))
      (node (ref "U1") (pin "141") (pinfunction "PC12/SPI3_MOSI/I2S3_SD/U3_CK/U5_TX/SDIO_CK/DCMI_D9_141") (pintype "passive"))
    )
    (net (code "48") (name "/SDIO_CMD(PD2)") (class "Default")
      (node (ref "1") (pin "3") (pinfunction "CMD_3") (pintype "passive"))
      (node (ref "R34") (pin "2") (pintype "passive"))
      (node (ref "U1") (pin "144") (pinfunction "PD2/TIM3_ETR/U5_RX/SDIO_CMD/DCMI_D11_144") (pintype "passive"))
    )
    (net (code "49") (name "/SDIO_D0(PC8)") (class "Default")
      (node (ref "1") (pin "7") (pinfunction "DATA0_7") (pintype "passive"))
      (node (ref "R35") (pin "2") (pintype "passive"))
      (node (ref "U1") (pin "117") (pinfunction "PC8/TIM3_CH3/TIM8_CH3/U6_CK/SDIO_D0/DCMI_D2_117") (pintype "passive"))
    )
    (net (code "50") (name "/SDIO_D1(PC9)") (class "Default")
      (node (ref "1") (pin "8") (pinfunction "DATA1_8") (pintype "passive"))
      (node (ref "R36") (pin "2") (pintype "passive"))
      (node (ref "U1") (pin "118") (pinfunction "PC9/MCO2/TIM3_CH4/TIM8_CH4/I2C3_SDA/I2S_CKIN/SDIO_D1/DCMI_D3_118") (pintype "passive"))
    )
    (net (code "51") (name "/SDIO_D2(PC10)") (class "Default")
      (node (ref "1") (pin "1") (pinfunction "DATA2_1") (pintype "passive"))
      (node (ref "R32") (pin "2") (pintype "passive"))
      (node (ref "U1") (pin "139") (pinfunction "PC10/SPI3_SCK/I2S3_CK/U3_TX/U4_TX/SDIO_D2/DCMI_D8/LCD_R2_139") (pintype "passive"))
    )
    (net (code "52") (name "/SDIO_D3(PC11)") (class "Default")
      (node (ref "1") (pin "2") (pinfunction "CD/DATA3_2") (pintype "passive"))
      (node (ref "R33") (pin "2") (pintype "passive"))
      (node (ref "U1") (pin "140") (pinfunction "PC11/I2S3ext_SD/SPI3_MISO/U3_RX/U4_RX/SDIO_D3/DCMI_D4_140") (pintype "passive"))
    )
    (net (code "53") (name "/SPI2_CLK(PB13)") (class "Default")
      (node (ref "*4") (pin "3") (pinfunction "CLK_3") (pintype "passive"))
      (node (ref "U1") (pin "93") (pinfunction "PB13/TIM1_CH1N/SPI2_SCK/I2S2_CK/U3_CTS/CAN2_TX/OTG_HS_ULPI_D6/ETH_MII_TXD1/ETH_RMII_TXD1/OTG_HS_VBUS_93") (pintype "passive"))
    )
    (net (code "54") (name "/SPI2_MISO(PB14)") (class "Default")
      (node (ref "*4") (pin "5") (pinfunction "MISO_5") (pintype "passive"))
      (node (ref "U1") (pin "94") (pinfunction "PB14/TIM1_CH2N/TIM8_CH2N/SPI2_MISO/I2S2ext_SD/U3_RTS/TIM12_CH1/OTG_HS_DM_94") (pintype "passive"))
    )
    (net (code "55") (name "/SPI2_MOSI(PB15)") (class "Default")
      (node (ref "*4") (pin "4") (pinfunction "MOSI_4") (pintype "passive"))
      (node (ref "U1") (pin "95") (pinfunction "PB15/RTC_REFIN/TIM1_CH3N/TIM8_CH3N/SPI2_MOSI/I2S2_SD/TIM12_CH2/OTG_HS_DP_95") (pintype "passive"))
    )
    (net (code "56") (name "/SPI2_NSS(PB12)") (class "Default")
      (node (ref "*4") (pin "6") (pinfunction "NSS_6") (pintype "passive"))
      (node (ref "U1") (pin "92") (pinfunction "PB12/TIM1_BKIN/I2C2_SMBA/SPI2_NSS/I2S2_WS/U3_CK/CAN2_RX/OTG_HS_ULPI_D5/ETH_MII_TXD0/ETH_RMII_TXD0/OTG_HS_ID_92") (pintype "passive"))
    )
    (net (code "57") (name "/SPI4_CLK(PE2)") (class "Default")
      (node (ref "*5") (pin "3") (pinfunction "CLK_3") (pintype "passive"))
      (node (ref "U1") (pin "1") (pinfunction "PE2/SPI4_SCK/SAI1_MCLK_A/ETH_MII_TXD3/FMC_A23_1") (pintype "passive"))
    )
    (net (code "58") (name "/SPI4_MISO(PE5)") (class "Default")
      (node (ref "*5") (pin "5") (pinfunction "MISO_5") (pintype "passive"))
      (node (ref "U1") (pin "4") (pinfunction "PE5/TIM9_CH1/SPI4_MISO/SAI1_SCK_A/FMC_A21/DCMI_D6/LCD_G0_4") (pintype "passive"))
    )
    (net (code "59") (name "/SPI4_MOSI(PE6)") (class "Default")
      (node (ref "*5") (pin "4") (pinfunction "MOSI_4") (pintype "passive"))
      (node (ref "U1") (pin "5") (pinfunction "PE6/TIM9_CH2/SPI4_MOSI/SAI1_SD_A/FMC_A22/DCMI_D7/LCD_G1_5") (pintype "passive"))
    )
    (net (code "60") (name "/SPI4_NSS(PE4)") (class "Default")
      (node (ref "*5") (pin "6") (pinfunction "NSS_6") (pintype "passive"))
      (node (ref "U1") (pin "3") (pinfunction "PE4/SPI4_NSS/SAI1_FS_A/FMC_A20/DCMI_D4/LCD_B0_3") (pintype "passive"))
    )
    (net (code "61") (name "/SPI5_CLK(PF7)") (class "Default")
      (node (ref "*6") (pin "3") (pinfunction "CLK_3") (pintype "passive"))
      (node (ref "U1") (pin "25") (pinfunction "PF7/TIM11_CH1/SPI5_SCK/SAI1_MCLK_B/U7_TX/FMC_NREG/ADC3_IN5_25") (pintype "passive"))
    )
    (net (code "62") (name "/SPI5_MISO(PF8)") (class "Default")
      (node (ref "*6") (pin "5") (pinfunction "MISO_5") (pintype "passive"))
      (node (ref "U1") (pin "26") (pinfunction "PF8/TIM13_CH1/SPI5_MISO/SAI1_SCK_B/FMC_NIOWR/ADC3_IN6_26") (pintype "passive"))
    )
    (net (code "63") (name "/SPI5_MOSI(PF9)") (class "Default")
      (node (ref "*6") (pin "4") (pinfunction "MOSI_4") (pintype "passive"))
      (node (ref "U1") (pin "27") (pinfunction "PF9/TIM14_CH1/SPI5_MOSI/SAI1_FS_B/FMC_CD/ADC3_IN7_27") (pintype "passive"))
    )
    (net (code "64") (name "/SPI5_NSS(PF6)") (class "Default")
      (node (ref "*6") (pin "6") (pinfunction "NSS_6") (pintype "passive"))
      (node (ref "U1") (pin "24") (pinfunction "PF6/TIM10_CH1/SPI5_NSS/SAI1_SD_B/U7_RX/FMC_NIORD/ADC3_IN4_24") (pintype "passive"))
    )
    (net (code "65") (name "/SPI6_CLK(PG13)") (class "Default")
      (node (ref "*7") (pin "3") (pinfunction "CLK_3") (pintype "passive"))
      (node (ref "U1") (pin "156") (pinfunction "PG13/SPI6_SCK/U6_CTS/ETH_MII_TXD0/ETH_RMII_TXD0/FMC_A24_156") (pintype "passive"))
    )
    (net (code "66") (name "/SPI6_MISO(PG12)") (class "Default")
      (node (ref "*7") (pin "5") (pinfunction "MISO_5") (pintype "passive"))
      (node (ref "U1") (pin "155") (pinfunction "PG12/SPI6_MISO/U6_RTS/FMC_NE4/LCD_B1/LCD_B4_155") (pintype "passive"))
    )
    (net (code "67") (name "/SPI6_MOSI(PG14)") (class "Default")
      (node (ref "*7") (pin "4") (pinfunction "MOSI_4") (pintype "passive"))
      (node (ref "U1") (pin "157") (pinfunction "PG14/SPI6_MOSI/U6_TX/ETH_MII_TXD1/ETH_RMII_TXD1/FMC_A25_157") (pintype "passive"))
    )
    (net (code "68") (name "/SPI6_NSS(PG8)") (class "Default")
      (node (ref "*7") (pin "6") (pinfunction "NSS_6") (pintype "passive"))
      (node (ref "U1") (pin "112") (pinfunction "PG8/SPI6_NSS/U6_RTS/ETH_PPS_OUT/FMC_SDCLK_112") (pintype "passive"))
    )
    (net (code "69") (name "/SWCLK(PA14)") (class "Default")
      (node (ref "R20") (pin "2") (pintype "passive"))
      (node (ref "U1") (pin "137") (pinfunction "PA14/JTCK/SWDCLK_137") (pintype "passive"))
    )
    (net (code "70") (name "/SWDIO(PA13)") (class "Default")
      (node (ref "R19") (pin "2") (pintype "passive"))
      (node (ref "U1") (pin "124") (pinfunction "PA13/JTMS/SWDIO_124") (pintype "passive"))
    )
    (net (code "71") (name "/TIM1_CH1(PE9)") (class "Default")
      (node (ref "J3") (pin "3") (pinfunction "3_3") (pintype "passive"))
      (node (ref "U1") (pin "70") (pinfunction "PE9/TIM1_CH1/FMC_D6_70") (pintype "passive"))
    )
    (net (code "72") (name "/TIM1_CH2(PE11)") (class "Default")
      (node (ref "J4") (pin "3") (pinfunction "3_3") (pintype "passive"))
      (node (ref "U1") (pin "74") (pinfunction "PE11/TIM1_CH2/SPI4_NSS/FMC_D8/LCD_G3_74") (pintype "passive"))
    )
    (net (code "73") (name "/TIM1_CH3(PE12)") (class "Default")
      (node (ref "J5") (pin "3") (pinfunction "3_3") (pintype "passive"))
      (node (ref "U1") (pin "75") (pinfunction "PE12/TIM1_CH3N/SPI4_SCK/FMC_D9/LCD_B4_75") (pintype "passive"))
    )
    (net (code "74") (name "/TIM1_CH4(PE14)") (class "Default")
      (node (ref "J6") (pin "3") (pinfunction "3_3") (pintype "passive"))
      (node (ref "U1") (pin "77") (pinfunction "PE14/TIM1_CH4/SPI4_MOSI/FMC_D11/LCD_CLK_77") (pintype "passive"))
    )
    (net (code "75") (name "/TIM2_CH1(PA0)") (class "Default")
      (node (ref "PWM2") (pin "1") (pinfunction "1_1") (pintype "passive"))
      (node (ref "U1") (pin "40") (pinfunction "PA0/WK_UP/TIM2_CH1/TIM2_ETR/TIM5_CH1/TIM8_ETR/U2_CTS/U4_TX/ETH_MII_CRS/ADC123_IN0_40") (pintype "passive"))
    )
    (net (code "76") (name "/TIM2_CH2(PA1)") (class "Default")
      (node (ref "PWM2") (pin "4") (pinfunction "4_4") (pintype "passive"))
      (node (ref "U1") (pin "41") (pinfunction "PA1/TIM2_CH2/TIM5_CH2/U2_RTS/U4_RX/ETH_MII_RX_CLK/ETH_RMII_REF_CLK/ADC123_IN1_41") (pintype "passive"))
    )
    (net (code "77") (name "/TIM2_CH3(PA2)") (class "Default")
      (node (ref "PWM2") (pin "7") (pinfunction "7_7") (pintype "passive"))
      (node (ref "U1") (pin "42") (pinfunction "PA2/TIM2_CH3/TIM5_CH3/TIM9_CH1/U2_TX/ETH_MDIO/ADC123_IN2_42") (pintype "passive"))
    )
    (net (code "78") (name "/TIM2_CH4(PA3)") (class "Default")
      (node (ref "PWM2") (pin "10") (pinfunction "10_10") (pintype "passive"))
      (node (ref "U1") (pin "47") (pinfunction "PA3/TIM2_CH4/TIM5_CH4/TIM9_CH2/U2_RX/OTG_HS_ULPI_D0/ETH_MII_COL/LCD_B5/ADC123_IN3_47") (pintype "passive"))
    )
    (net (code "79") (name "/TIM4_CH1(PD12)") (class "Default")
      (node (ref "PWM1") (pin "3") (pinfunction "3_3") (pintype "passive"))
      (node (ref "U1") (pin "100") (pinfunction "PD12/TIM4_CH1/U3_RTS/FMC_A17_100") (pintype "passive"))
    )
    (net (code "80") (name "/TIM4_CH2(PD13)") (class "Default")
      (node (ref "PWM1") (pin "6") (pinfunction "6_6") (pintype "passive"))
      (node (ref "U1") (pin "101") (pinfunction "PD13/TIM4_CH2/FMC_A18_101") (pintype "passive"))
    )
    (net (code "81") (name "/TIM4_CH3(PD14)") (class "Default")
      (node (ref "PWM1") (pin "9") (pinfunction "9_9") (pintype "passive"))
      (node (ref "U1") (pin "104") (pinfunction "PD14/TIM4_CH3/FMC_D0_104") (pintype "passive"))
    )
    (net (code "82") (name "/TIM4_CH4(PD15)") (class "Default")
      (node (ref "PWM1") (pin "12") (pinfunction "12_12") (pintype "passive"))
      (node (ref "U1") (pin "105") (pinfunction "PD15/TIM4_CH4/FMC_D1_105") (pintype "passive"))
    )
    (net (code "83") (name "/TIM5_CH1(PH10)") (class "Default")
      (node (ref "PWM1") (pin "15") (pinfunction "15_15") (pintype "passive"))
      (node (ref "U1") (pin "87") (pinfunction "PH10/TIM5_CH1/FMC_D18/DCMI_D1/LCD_R4_87") (pintype "passive"))
    )
    (net (code "84") (name "/TIM5_CH2(PH11)") (class "Default")
      (node (ref "PWM1") (pin "18") (pinfunction "18_18") (pintype "passive"))
      (node (ref "U1") (pin "88") (pinfunction "PH11/TIM5_CH2/FMC_D19/DCMI_D2/LCD_R5_88") (pintype "passive"))
    )
    (net (code "85") (name "/TIM5_CH3(PH12)") (class "Default")
      (node (ref "PWM1") (pin "21") (pinfunction "21_21") (pintype "passive"))
      (node (ref "U1") (pin "89") (pinfunction "PH12/TIM5_CH3/FMC_D20/DCMI_D3/LCD_R6_89") (pintype "passive"))
    )
    (net (code "86") (name "/TIM5_CH4(PIO)") (class "Default")
      (node (ref "PWM1") (pin "24") (pinfunction "24_24") (pintype "passive"))
      (node (ref "U1") (pin "131") (pinfunction "PI0/TIM5_CH4/SPI2_NSS/I2S2_WS/FMC_D24/DCMI_D13/LCD_G5_131") (pintype "passive"))
    )
    (net (code "87") (name "/TIM8_CH1(PI5)") (class "Default")
      (node (ref "PWM2") (pin "13") (pinfunction "13_13") (pintype "passive"))
      (node (ref "U1") (pin "174") (pinfunction "PI5/TIM8_CH1/FMC_NBL3/DCMI_VSYNC/LCD_B5_174") (pintype "passive"))
    )
    (net (code "88") (name "/TIM8_CH2(PI6)") (class "Default")
      (node (ref "PWM2") (pin "16") (pinfunction "16_16") (pintype "passive"))
      (node (ref "U1") (pin "175") (pinfunction "PI6/TIM8_CH2/FMC_D28/DCMI_D6/LCD_B6_175") (pintype "passive"))
    )
    (net (code "89") (name "/TIM8_CH3(PI7)") (class "Default")
      (node (ref "PWM2") (pin "19") (pinfunction "19_19") (pintype "passive"))
      (node (ref "U1") (pin "176") (pinfunction "PI7/TIM8_CH3/FMC_D29/DCMI_D7/LCD_B7_176") (pintype "passive"))
    )
    (net (code "90") (name "/TIM8_CH4(PI2)") (class "Default")
      (node (ref "PWM2") (pin "22") (pinfunction "22_22") (pintype "passive"))
      (node (ref "U1") (pin "133") (pinfunction "PI2/TIM8_CH4/SPI2_MISO/I2S2ext_SD/FMC_D26/DCMI_D9/LCD_G7_133") (pintype "passive"))
    )
    (net (code "91") (name "/USART1_RX(PA10)") (class "Default")
      (node (ref "J7") (pin "3") (pinfunction "3_3") (pintype "passive"))
      (node (ref "U1") (pin "121") (pinfunction "PA10/TIM1_CH3/U1_RX/OTG_FS_ID/DCMI_D1_121") (pintype "passive"))
    )
    (net (code "92") (name "/USART1_TX(PA9)") (class "Default")
      (node (ref "J7") (pin "4") (pinfunction "4_4") (pintype "passive"))
      (node (ref "U1") (pin "120") (pinfunction "PA9/TIM1_CH2/I2C3_SMBA/U1_TX/DCMI_D0/OTG_FS_VBUS_120") (pintype "passive"))
    )
    (net (code "93") (name "/USART2_RX") (class "Default")
      (node (ref "Q1") (pin "3") (pinfunction "C_3") (pintype "passive"))
      (node (ref "R2") (pin "1") (pintype "passive"))
      (node (ref "U1") (pin "150") (pinfunction "PD6/SPI3_MOSI/I2S3_SD/SAI1_SD_A/U2_RX/FMC_NWAIT/DCMI_D10/LCD_B2_150") (pintype "passive"))
    )
    (net (code "94") (name "/USART3_RX(PD9）") (class "Default")
      (node (ref "J8") (pin "3") (pinfunction "3_3") (pintype "passive"))
      (node (ref "U1") (pin "97") (pinfunction "PD9/U3_RX/FMC_D14_97") (pintype "passive"))
    )
    (net (code "95") (name "/USART3_TX(PD8)") (class "Default")
      (node (ref "J8") (pin "4") (pinfunction "4_4") (pintype "passive"))
      (node (ref "U1") (pin "96") (pinfunction "PD8/U3_TX/FMC_D13_96") (pintype "passive"))
    )
    (net (code "96") (name "/USART6_RX(PC7)") (class "Default")
      (node (ref "J10") (pin "3") (pinfunction "3_3") (pintype "passive"))
      (node (ref "U1") (pin "116") (pinfunction "PC7/TIM3_CH2/TIM8_CH2/I2S3_MCK/U6_RX/SDIO_D7/DCMI_D1/LCD_G6_116") (pintype "passive"))
    )
    (net (code "97") (name "/USART6_TX(PC6)") (class "Default")
      (node (ref "J10") (pin "4") (pinfunction "4_4") (pintype "passive"))
      (node (ref "U1") (pin "115") (pinfunction "PC6/TIM3_CH1/TIM8_CH1/I2S2_MCK/U6_TX/SDIO_D6/DCMI_D0/LCD_HSYNC_115") (pintype "passive"))
    )
    (net (code "98") (name "/USART7_RX(PE7)") (class "Default")
      (node (ref "J9") (pin "3") (pinfunction "3_3") (pintype "passive"))
      (node (ref "U1") (pin "68") (pinfunction "PE7/TIM1_ETR/U7_RX/FMC_D4_68") (pintype "passive"))
    )
    (net (code "99") (name "/USART7_TX(PE8)") (class "Default")
      (node (ref "J9") (pin "4") (pinfunction "4_4") (pintype "passive"))
      (node (ref "U1") (pin "69") (pinfunction "PE8/TIM1_CH1N/U7_TX/FMC_D5_69") (pintype "passive"))
    )
    (net (code "100") (name "/USART8_RX(PE0)") (class "Default")
      (node (ref "J11") (pin "3") (pinfunction "3_3") (pintype "passive"))
      (node (ref "U1") (pin "169") (pinfunction "PE0/TIM4_ETR/U8_RX/FMC_NBL0/DCMI_D2_169") (pintype "passive"))
    )
    (net (code "101") (name "/USART8_TX(PE1)") (class "Default")
      (node (ref "J11") (pin "4") (pinfunction "4_4") (pintype "passive"))
      (node (ref "U1") (pin "170") (pinfunction "PE1/U8_TX/FMC_NBL1/DCMI_D3_170") (pintype "passive"))
    )
    (net (code "102") (name "/USB_D+(PA12)") (class "Default")
      (node (ref "R28") (pin "2") (pintype "passive"))
      (node (ref "U1") (pin "123") (pinfunction "PA12/TIM1_ETR/U1_RTS/CAN1_TX/LCD_R5/OTG_FS_DP_123") (pintype "passive"))
    )
    (net (code "103") (name "/USB_D-(PA11)") (class "Default")
      (node (ref "R27") (pin "2") (pintype "passive"))
      (node (ref "U1") (pin "122") (pinfunction "PA11/TIM1_CH4/U1_CTS/CAN1_RX/LCD_R4/OTG_FS_DM_122") (pintype "passive"))
    )
    (net (code "104") (name "/VDDA") (class "Default")
      (node (ref "C10") (pin "2") (pintype "passive"))
      (node (ref "C9") (pin "2") (pintype "passive"))
      (node (ref "R8") (pin "1") (pintype "passive"))
      (node (ref "U1") (pin "39") (pinfunction "VDDA_39") (pintype "passive"))
    )
    (net (code "105") (name "GND") (class "Default")
      (node (ref "*2") (pin "6") (pinfunction "GND_6") (pintype "passive"))
      (node (ref "*4") (pin "1") (pinfunction "GND_1") (pintype "passive"))
      (node (ref "*5") (pin "1") (pinfunction "GND_1") (pintype "passive"))
      (node (ref "*6") (pin "1") (pinfunction "GND_1") (pintype "passive"))
      (node (ref "*7") (pin "1") (pinfunction "GND_1") (pintype "passive"))
      (node (ref "*9") (pin "2") (pinfunction "GND_2") (pintype "passive"))
      (node (ref "1") (pin "10") (pinfunction "GND_10") (pintype "passive"))
      (node (ref "1") (pin "6") (pinfunction "VSS_6") (pintype "passive"))
      (node (ref "2") (pin "1") (pintype "passive"))
      (node (ref "3") (pin "1") (pintype "passive"))
      (node (ref "C1") (pin "1") (pintype "passive"))
      (node (ref "C10") (pin "1") (pintype "passive"))
      (node (ref "C11") (pin "1") (pintype "passive"))
      (node (ref "C12") (pin "1") (pintype "passive"))
      (node (ref "C13") (pin "1") (pintype "passive"))
      (node (ref "C14") (pin "1") (pintype "passive"))
      (node (ref "C15") (pin "1") (pintype "passive"))
      (node (ref "C16") (pin "2") (pintype "passive"))
      (node (ref "C17") (pin "1") (pintype "passive"))
      (node (ref "C18") (pin "1") (pintype "passive"))
      (node (ref "C19") (pin "1") (pintype "passive"))
      (node (ref "C2") (pin "1") (pintype "passive"))
      (node (ref "C20") (pin "1") (pintype "passive"))
      (node (ref "C21") (pin "1") (pintype "passive"))
      (node (ref "C22") (pin "1") (pintype "passive"))
      (node (ref "C23") (pin "1") (pintype "passive"))
      (node (ref "C24") (pin "1") (pintype "passive"))
      (node (ref "C25") (pin "1") (pintype "passive"))
      (node (ref "C26") (pin "1") (pintype "passive"))
      (node (ref "C27") (pin "1") (pintype "passive"))
      (node (ref "C28") (pin "1") (pintype "passive"))
      (node (ref "C3") (pin "1") (pintype "passive"))
      (node (ref "C4") (pin "1") (pintype "passive"))
      (node (ref "C5") (pin "1") (pintype "passive"))
      (node (ref "C6") (pin "1") (pintype "passive"))
      (node (ref "C7") (pin "2") (pintype "passive"))
      (node (ref "C8") (pin "2") (pintype "passive"))
      (node (ref "C9") (pin "1") (pintype "passive"))
      (node (ref "CAN2") (pin "3") (pinfunction "3_3") (pintype "passive"))
      (node (ref "CAP1") (pin "C") (pinfunction "-_C") (pintype "passive"))
      (node (ref "CAP2") (pin "C") (pinfunction "-_C") (pintype "passive"))
      (node (ref "CAP3") (pin "C") (pinfunction "-_C") (pintype "passive"))
      (node (ref "DBUS1") (pin "3") (pinfunction "3_3") (pintype "passive"))
      (node (ref "IIC1") (pin "2") (pinfunction "2_2") (pintype "passive"))
      (node (ref "IIC2") (pin "2") (pinfunction "2_2") (pintype "passive"))
      (node (ref "IIC3") (pin "2") (pinfunction "2_2") (pintype "passive"))
      (node (ref "J1") (pin "2") (pinfunction "GND_2") (pintype "passive"))
      (node (ref "J1") (pin "8") (pinfunction "RS_8") (pintype "passive"))
      (node (ref "J10") (pin "2") (pinfunction "2_2") (pintype "passive"))
      (node (ref "J11") (pin "2") (pinfunction "2_2") (pintype "passive"))
      (node (ref "J12") (pin "1") (pinfunction "1_1") (pintype "passive"))
      (node (ref "J13") (pin "1") (pinfunction "1_1") (pintype "passive"))
      (node (ref "J2") (pin "2") (pinfunction "GND_2") (pintype "passive"))
      (node (ref "J2") (pin "8") (pinfunction "RS_8") (pintype "passive"))
      (node (ref "J7") (pin "2") (pinfunction "2_2") (pintype "passive"))
      (node (ref "J8") (pin "2") (pinfunction "2_2") (pintype "passive"))
      (node (ref "J9") (pin "2") (pinfunction "2_2") (pintype "passive"))
      (node (ref "OLED1") (pin "6") (pinfunction "6_6") (pintype "passive"))
      (node (ref "PWR") (pin "2") (pinfunction "2_2") (pintype "passive"))
      (node (ref "Q1") (pin "2") (pinfunction "E_2") (pintype "passive"))
      (node (ref "Q2") (pin "2") (pinfunction "E_2") (pintype "passive"))
      (node (ref "R21") (pin "2") (pintype "passive"))
      (node (ref "R30") (pin "2") (pintype "passive"))
      (node (ref "R31") (pin "1") (pintype "passive"))
      (node (ref "R39") (pin "2") (pintype "passive"))
      (node (ref "R5") (pin "1") (pintype "passive"))
      (node (ref "R6") (pin "2") (pintype "passive"))
      (node (ref "RST1") (pin "2") (pinfunction "2_2") (pintype "passive"))
      (node (ref "U1") (pin "102") (pinfunction "VSS_102") (pintype "passive"))
      (node (ref "U1") (pin "113") (pinfunction "VSS_113") (pintype "passive"))
      (node (ref "U1") (pin "126") (pinfunction "VSS_126") (pintype "passive"))
      (node (ref "U1") (pin "135") (pinfunction "VSS_135") (pintype "passive"))
      (node (ref "U1") (pin "14") (pinfunction "VSS_14") (pintype "passive"))
      (node (ref "U1") (pin "148") (pinfunction "VSS_148") (pintype "passive"))
      (node (ref "U1") (pin "158") (pinfunction "VSS_158") (pintype "passive"))
      (node (ref "U1") (pin "22") (pinfunction "VSS_22") (pintype "passive"))
      (node (ref "U1") (pin "37") (pinfunction "VSSA_37") (pintype "passive"))
      (node (ref "U1") (pin "61") (pinfunction "VSS_61") (pintype "passive"))
      (node (ref "U1") (pin "71") (pinfunction "VSS_71") (pintype "passive"))
      (node (ref "U1") (pin "90") (pinfunction "VSS_90") (pintype "passive"))
      (node (ref "U2") (pin "1") (pinfunction "GND_1") (pintype "passive"))
      (node (ref "USB") (pin "5") (pinfunction "GND_5") (pintype "power_in"))
      (node (ref "Y2") (pin "2") (pinfunction "GND_2") (pintype "passive"))
      (node (ref "Y2") (pin "4") (pinfunction "GND_4") (pintype "passive"))
    )
    (net (code "106") (name "Net-(*3-Pad1)") (class "Default")
      (node (ref "*3") (pin "1") (pinfunction "1_1") (pintype "passive"))
      (node (ref "R19") (pin "1") (pintype "passive"))
    )
    (net (code "107") (name "Net-(*3-Pad2)") (class "Default")
      (node (ref "*3") (pin "2") (pinfunction "2_2") (pintype "passive"))
      (node (ref "R20") (pin "1") (pintype "passive"))
    )
    (net (code "108") (name "Net-(*3-Pad3)") (class "Default")
      (node (ref "*3") (pin "3") (pinfunction "3_3") (pintype "passive"))
      (node (ref "R21") (pin "1") (pintype "passive"))
    )
    (net (code "109") (name "Net-(DBUS1-Pad1)") (class "Default")
      (node (ref "DBUS1") (pin "1") (pinfunction "1_1") (pintype "passive"))
      (node (ref "R3") (pin "2") (pintype "passive"))
    )
    (net (code "110") (name "Net-(LED1-Pad1)") (class "Default")
      (node (ref "LED1") (pin "1") (pinfunction "1_1") (pintype "passive"))
      (node (ref "R9") (pin "2") (pintype "passive"))
    )
    (net (code "111") (name "Net-(LED2-Pad1)") (class "Default")
      (node (ref "LED2") (pin "1") (pinfunction "1_1") (pintype "passive"))
      (node (ref "R10") (pin "2") (pintype "passive"))
    )
    (net (code "112") (name "Net-(LED3-Pad1)") (class "Default")
      (node (ref "LED3") (pin "1") (pinfunction "1_1") (pintype "passive"))
      (node (ref "R11") (pin "2") (pintype "passive"))
    )
    (net (code "113") (name "Net-(LED4-Pad1)") (class "Default")
      (node (ref "LED4") (pin "1") (pinfunction "1_1") (pintype "passive"))
      (node (ref "R13") (pin "2") (pintype "passive"))
    )
    (net (code "114") (name "Net-(LED5-Pad1)") (class "Default")
      (node (ref "LED5") (pin "1") (pinfunction "1_1") (pintype "passive"))
      (node (ref "R14") (pin "2") (pintype "passive"))
    )
    (net (code "115") (name "Net-(LED6-Pad1)") (class "Default")
      (node (ref "LED6") (pin "1") (pinfunction "1_1") (pintype "passive"))
      (node (ref "R15") (pin "2") (pintype "passive"))
    )
    (net (code "116") (name "Net-(LED7-Pad1)") (class "Default")
      (node (ref "LED7") (pin "1") (pinfunction "1_1") (pintype "passive"))
      (node (ref "R17") (pin "2") (pintype "passive"))
    )
    (net (code "117") (name "Net-(LED8-Pad1)") (class "Default")
      (node (ref "LED8") (pin "1") (pinfunction "1_1") (pintype "passive"))
      (node (ref "R18") (pin "2") (pintype "passive"))
    )
    (net (code "118") (name "Net-(PWR-Pad1)") (class "Default")
      (node (ref "PWR") (pin "1") (pinfunction "1_1") (pintype "passive"))
      (node (ref "R29") (pin "2") (pintype "passive"))
    )
    (net (code "119") (name "Net-(Q1-B)") (class "Default")
      (node (ref "Q1") (pin "1") (pinfunction "B_1") (pintype "passive"))
      (node (ref "R3") (pin "1") (pintype "passive"))
    )
    (net (code "120") (name "Net-(Q2-B)") (class "Default")
      (node (ref "Q2") (pin "1") (pinfunction "B_1") (pintype "passive"))
      (node (ref "R4") (pin "2") (pintype "passive"))
      (node (ref "R5") (pin "2") (pintype "passive"))
    )
    (net (code "121") (name "Net-(Q2-C)") (class "Default")
      (node (ref "*1") (pin "2") (pinfunction "2_2") (pintype "passive"))
      (node (ref "Q2") (pin "3") (pinfunction "C_3") (pintype "passive"))
      (node (ref "Z1") (pin "1") (pinfunction "A_1") (pintype "passive"))
    )
    (net (code "122") (name "Net-(RGB-BLU)") (class "Default")
      (node (ref "R23") (pin "2") (pintype "passive"))
      (node (ref "RGB") (pin "B") (pinfunction "BLU_B") (pintype "passive"))
    )
    (net (code "123") (name "Net-(RGB-GRN)") (class "Default")
      (node (ref "R24") (pin "2") (pintype "passive"))
      (node (ref "RGB") (pin "G") (pinfunction "GRN_G") (pintype "passive"))
    )
    (net (code "124") (name "Net-(RGB-RED)") (class "Default")
      (node (ref "R22") (pin "2") (pintype "passive"))
      (node (ref "RGB") (pin "R") (pinfunction "RED_R") (pintype "passive"))
    )
    (net (code "125") (name "Net-(U1-BYPASS_REG)") (class "Default")
      (node (ref "R6") (pin "1") (pintype "passive"))
      (node (ref "U1") (pin "48") (pinfunction "BYPASS_REG_48") (pintype "passive"))
    )
    (net (code "126") (name "Net-(U1-PC14{slash}OSC32_IN)") (class "Default")
      (node (ref "C12") (pin "2") (pintype "passive"))
      (node (ref "U1") (pin "9") (pinfunction "PC14/OSC32_IN_9") (pintype "passive"))
      (node (ref "Y1") (pin "2") (pinfunction "OSC2_2") (pintype "passive"))
    )
    (net (code "127") (name "Net-(U1-PC15{slash}OSC32_OUT)") (class "Default")
      (node (ref "C13") (pin "2") (pintype "passive"))
      (node (ref "U1") (pin "10") (pinfunction "PC15/OSC32_OUT_10") (pintype "passive"))
      (node (ref "Y1") (pin "1") (pinfunction "OSC1_1") (pintype "passive"))
    )
    (net (code "128") (name "Net-(U1-PDR_ON)") (class "Default")
      (node (ref "R12") (pin "1") (pintype "passive"))
      (node (ref "U1") (pin "171") (pinfunction "PDR_ON_171") (pintype "passive"))
    )
    (net (code "129") (name "Net-(U1-PH0{slash}OSC_IN)") (class "Default")
      (node (ref "C14") (pin "2") (pintype "passive"))
      (node (ref "U1") (pin "29") (pinfunction "PH0/OSC_IN_29") (pintype "passive"))
      (node (ref "Y2") (pin "3") (pinfunction "HOT_3") (pintype "passive"))
    )
    (net (code "130") (name "Net-(U1-PH1{slash}OSC_OUT)") (class "Default")
      (node (ref "C15") (pin "2") (pintype "passive"))
      (node (ref "U1") (pin "30") (pinfunction "PH1/OSC_OUT_30") (pintype "passive"))
      (node (ref "Y2") (pin "1") (pinfunction "HOT_1") (pintype "passive"))
    )
    (net (code "131") (name "Net-(U1-VCAP_1)") (class "Default")
      (node (ref "C7") (pin "1") (pintype "passive"))
      (node (ref "U1") (pin "81") (pinfunction "VCAP_1_81") (pintype "passive"))
    )
    (net (code "132") (name "Net-(U1-VCAP_2)") (class "Default")
      (node (ref "C8") (pin "1") (pintype "passive"))
      (node (ref "U1") (pin "125") (pinfunction "VCAP_2_125") (pintype "passive"))
    )
    (net (code "133") (name "Net-(USB-D+)") (class "Default")
      (node (ref "R28") (pin "1") (pintype "passive"))
      (node (ref "USB") (pin "3") (pinfunction "D+_3") (pintype "passive"))
    )
    (net (code "134") (name "Net-(USB-D-)") (class "Default")
      (node (ref "R27") (pin "1") (pintype "passive"))
      (node (ref "USB") (pin "2") (pinfunction "D-_2") (pintype "passive"))
    )
    (net (code "135") (name "PGND") (class "Default")
      (node (ref "*8") (pin "2") (pinfunction "GND_2") (pintype "passive"))
      (node (ref "J3") (pin "1") (pinfunction "1_1") (pintype "passive"))
      (node (ref "J4") (pin "1") (pinfunction "1_1") (pintype "passive"))
      (node (ref "J5") (pin "1") (pinfunction "1_1") (pintype "passive"))
      (node (ref "J6") (pin "1") (pinfunction "1_1") (pintype "passive"))
      (node (ref "PWM1") (pin "1") (pinfunction "1_1") (pintype "passive"))
      (node (ref "PWM1") (pin "10") (pinfunction "10_10") (pintype "passive"))
      (node (ref "PWM1") (pin "13") (pinfunction "13_13") (pintype "passive"))
      (node (ref "PWM1") (pin "16") (pinfunction "16_16") (pintype "passive"))
      (node (ref "PWM1") (pin "19") (pinfunction "19_19") (pintype "passive"))
      (node (ref "PWM1") (pin "22") (pinfunction "22_22") (pintype "passive"))
      (node (ref "PWM1") (pin "4") (pinfunction "4_4") (pintype "passive"))
      (node (ref "PWM1") (pin "7") (pinfunction "7_7") (pintype "passive"))
      (node (ref "PWM2") (pin "12") (pinfunction "12_12") (pintype "passive"))
      (node (ref "PWM2") (pin "15") (pinfunction "15_15") (pintype "passive"))
      (node (ref "PWM2") (pin "18") (pinfunction "18_18") (pintype "passive"))
      (node (ref "PWM2") (pin "21") (pinfunction "21_21") (pintype "passive"))
      (node (ref "PWM2") (pin "24") (pinfunction "24_24") (pintype "passive"))
      (node (ref "PWM2") (pin "3") (pinfunction "3_3") (pintype "passive"))
      (node (ref "PWM2") (pin "6") (pinfunction "6_6") (pintype "passive"))
      (node (ref "PWM2") (pin "9") (pinfunction "9_9") (pintype "passive"))
      (node (ref "R39") (pin "1") (pintype "passive"))
    )
    (net (code "136") (name "PWM_5V") (class "Default")
      (node (ref "*8") (pin "1") (pinfunction "PWM_VCC5_1") (pintype "passive"))
      (node (ref "J3") (pin "2") (pinfunction "2_2") (pintype "passive"))
      (node (ref "J4") (pin "2") (pinfunction "2_2") (pintype "passive"))
      (node (ref "J5") (pin "2") (pinfunction "2_2") (pintype "passive"))
      (node (ref "J6") (pin "2") (pinfunction "2_2") (pintype "passive"))
      (node (ref "PWM1") (pin "11") (pinfunction "11_11") (pintype "passive"))
      (node (ref "PWM1") (pin "14") (pinfunction "14_14") (pintype "passive"))
      (node (ref "PWM1") (pin "17") (pinfunction "17_17") (pintype "passive"))
      (node (ref "PWM1") (pin "2") (pinfunction "2_2") (pintype "passive"))
      (node (ref "PWM1") (pin "20") (pinfunction "20_20") (pintype "passive"))
      (node (ref "PWM1") (pin "23") (pinfunction "23_23") (pintype "passive"))
      (node (ref "PWM1") (pin "5") (pinfunction "5_5") (pintype "passive"))
      (node (ref "PWM1") (pin "8") (pinfunction "8_8") (pintype "passive"))
      (node (ref "PWM2") (pin "11") (pinfunction "11_11") (pintype "passive"))
      (node (ref "PWM2") (pin "14") (pinfunction "14_14") (pintype "passive"))
      (node (ref "PWM2") (pin "17") (pinfunction "17_17") (pintype "passive"))
      (node (ref "PWM2") (pin "2") (pinfunction "2_2") (pintype "passive"))
      (node (ref "PWM2") (pin "20") (pinfunction "20_20") (pintype "passive"))
      (node (ref "PWM2") (pin "23") (pinfunction "23_23") (pintype "passive"))
      (node (ref "PWM2") (pin "5") (pinfunction "5_5") (pintype "passive"))
      (node (ref "PWM2") (pin "8") (pinfunction "8_8") (pintype "passive"))
    )
    (net (code "137") (name "VCC_3.3M") (class "Default")
      (node (ref "*3") (pin "4") (pinfunction "4_4") (pintype "passive"))
      (node (ref "1") (pin "4") (pinfunction "VDD_4") (pintype "passive"))
      (node (ref "3") (pin "2") (pintype "passive"))
      (node (ref "C17") (pin "2") (pintype "passive"))
      (node (ref "C18") (pin "2") (pintype "passive"))
      (node (ref "C19") (pin "2") (pintype "passive"))
      (node (ref "C20") (pin "2") (pintype "passive"))
      (node (ref "C21") (pin "2") (pintype "passive"))
      (node (ref "C22") (pin "2") (pintype "passive"))
      (node (ref "C23") (pin "2") (pintype "passive"))
      (node (ref "C24") (pin "2") (pintype "passive"))
      (node (ref "C25") (pin "2") (pintype "passive"))
      (node (ref "C26") (pin "2") (pintype "passive"))
      (node (ref "C27") (pin "2") (pintype "passive"))
      (node (ref "C28") (pin "2") (pintype "passive"))
      (node (ref "C3") (pin "2") (pintype "passive"))
      (node (ref "C4") (pin "2") (pintype "passive"))
      (node (ref "C5") (pin "2") (pintype "passive"))
      (node (ref "CAP2") (pin "A") (pinfunction "+_A") (pintype "passive"))
      (node (ref "CAP3") (pin "A") (pinfunction "+_A") (pintype "passive"))
      (node (ref "KEY1") (pin "1") (pinfunction "1_1") (pintype "passive"))
      (node (ref "KEY2") (pin "1") (pinfunction "1_1") (pintype "passive"))
      (node (ref "KEY3") (pin "1") (pinfunction "1_1") (pintype "passive"))
      (node (ref "KEY4") (pin "1") (pinfunction "1_1") (pintype "passive"))
      (node (ref "OLED1") (pin "7") (pinfunction "7_7") (pintype "passive"))
      (node (ref "R1") (pin "2") (pintype "passive"))
      (node (ref "R10") (pin "1") (pintype "passive"))
      (node (ref "R11") (pin "1") (pintype "passive"))
      (node (ref "R12") (pin "2") (pintype "passive"))
      (node (ref "R13") (pin "1") (pintype "passive"))
      (node (ref "R14") (pin "1") (pintype "passive"))
      (node (ref "R15") (pin "1") (pintype "passive"))
      (node (ref "R17") (pin "1") (pintype "passive"))
      (node (ref "R18") (pin "1") (pintype "passive"))
      (node (ref "R2") (pin "2") (pintype "passive"))
      (node (ref "R25") (pin "2") (pintype "passive"))
      (node (ref "R26") (pin "1") (pintype "passive"))
      (node (ref "R29") (pin "1") (pintype "passive"))
      (node (ref "R32") (pin "1") (pintype "passive"))
      (node (ref "R33") (pin "1") (pintype "passive"))
      (node (ref "R34") (pin "1") (pintype "passive"))
      (node (ref "R35") (pin "1") (pintype "passive"))
      (node (ref "R36") (pin "1") (pintype "passive"))
      (node (ref "R8") (pin "2") (pintype "passive"))
      (node (ref "R9") (pin "1") (pintype "passive"))
      (node (ref "RGB") (pin "A") (pinfunction "A_A") (pintype "passive"))
      (node (ref "U1") (pin "103") (pinfunction "VDD_103") (pintype "passive"))
      (node (ref "U1") (pin "114") (pinfunction "VDD_114") (pintype "passive"))
      (node (ref "U1") (pin "127") (pinfunction "VDD_127") (pintype "passive"))
      (node (ref "U1") (pin "136") (pinfunction "VDD_136") (pintype "passive"))
      (node (ref "U1") (pin "149") (pinfunction "VDD_149") (pintype "passive"))
      (node (ref "U1") (pin "15") (pinfunction "VDD_15") (pintype "passive"))
      (node (ref "U1") (pin "159") (pinfunction "VDD_159") (pintype "passive"))
      (node (ref "U1") (pin "172") (pinfunction "VDD_172") (pintype "passive"))
      (node (ref "U1") (pin "23") (pinfunction "VDD_23") (pintype "passive"))
      (node (ref "U1") (pin "36") (pinfunction "VDD_36") (pintype "passive"))
      (node (ref "U1") (pin "38") (pinfunction "VREF+_38") (pintype "passive"))
      (node (ref "U1") (pin "49") (pinfunction "VDD_49") (pintype "passive"))
      (node (ref "U1") (pin "6") (pinfunction "VBAT_6") (pintype "passive"))
      (node (ref "U1") (pin "62") (pinfunction "VDD_62") (pintype "passive"))
      (node (ref "U1") (pin "72") (pinfunction "VDD_72") (pintype "passive"))
      (node (ref "U1") (pin "82") (pinfunction "VDD_82") (pintype "passive"))
      (node (ref "U1") (pin "91") (pinfunction "VDD_91") (pintype "passive"))
      (node (ref "U2") (pin "2") (pinfunction "OUT_2") (pintype "passive"))
    )
    (net (code "138") (name "VCC_5V") (class "Default")
      (node (ref "*1") (pin "1") (pinfunction "1_1") (pintype "passive"))
      (node (ref "*4") (pin "2") (pinfunction "VCC_2") (pintype "passive"))
      (node (ref "*5") (pin "2") (pinfunction "VCC_2") (pintype "passive"))
      (node (ref "*6") (pin "2") (pinfunction "VCC_2") (pintype "passive"))
      (node (ref "*7") (pin "2") (pinfunction "VCC_2") (pintype "passive"))
      (node (ref "*9") (pin "1") (pinfunction "MCU_5V_1") (pintype "passive"))
      (node (ref "2") (pin "2") (pintype "passive"))
      (node (ref "C1") (pin "2") (pintype "passive"))
      (node (ref "C11") (pin "2") (pintype "passive"))
      (node (ref "C16") (pin "1") (pintype "passive"))
      (node (ref "C6") (pin "2") (pintype "passive"))
      (node (ref "CAN2") (pin "4") (pinfunction "4_4") (pintype "passive"))
      (node (ref "CAP1") (pin "A") (pinfunction "+_A") (pintype "passive"))
      (node (ref "DBUS1") (pin "2") (pinfunction "2_2") (pintype "passive"))
      (node (ref "IIC1") (pin "1") (pinfunction "1_1") (pintype "passive"))
      (node (ref "IIC2") (pin "1") (pinfunction "1_1") (pintype "passive"))
      (node (ref "IIC3") (pin "1") (pinfunction "1_1") (pintype "passive"))
      (node (ref "J1") (pin "3") (pinfunction "VCC_3") (pintype "passive"))
      (node (ref "J10") (pin "1") (pinfunction "1_1") (pintype "passive"))
      (node (ref "J11") (pin "1") (pinfunction "1_1") (pintype "passive"))
      (node (ref "J12") (pin "2") (pinfunction "2_2") (pintype "passive"))
      (node (ref "J13") (pin "2") (pinfunction "2_2") (pintype "passive"))
      (node (ref "J2") (pin "3") (pinfunction "VCC_3") (pintype "passive"))
      (node (ref "J7") (pin "1") (pinfunction "1_1") (pintype "passive"))
      (node (ref "J8") (pin "1") (pinfunction "1_1") (pintype "passive"))
      (node (ref "J9") (pin "1") (pinfunction "1_1") (pintype "passive"))
      (node (ref "U2") (pin "3") (pinfunction "IN_3") (pintype "passive"))
      (node (ref "USB") (pin "1") (pinfunction "5V_1") (pintype "power_in"))
      (node (ref "Z1") (pin "2") (pinfunction "C_2") (pintype "passive"))
    )
    (net (code "139") (name "unconnected-(1-Card_Detectuon-Pad9)") (class "Default")
      (node (ref "1") (pin "9") (pinfunction "Card_Detectuon_9") (pintype "passive+no_connect"))
    )
    (net (code "140") (name "unconnected-(J1-Vref-Pad5)") (class "Default")
      (node (ref "J1") (pin "5") (pinfunction "Vref_5") (pintype "passive"))
    )
    (net (code "141") (name "unconnected-(J2-Vref-Pad5)") (class "Default")
      (node (ref "J2") (pin "5") (pinfunction "Vref_5") (pintype "passive"))
    )
    (net (code "142") (name "unconnected-(U1-PA8{slash}MCO1{slash}TIM1_CH1{slash}I2C3_SCL{slash}U1_CK{slash}OTG_FS_SOF{slash}LCD_R6-Pad119)") (class "Default")
      (node (ref "U1") (pin "119") (pinfunction "PA8/MCO1/TIM1_CH1/I2C3_SCL/U1_CK/OTG_FS_SOF/LCD_R6_119") (pintype "passive+no_connect"))
    )
    (net (code "143") (name "unconnected-(U1-PA15{slash}JTDI{slash}TIM2_CH1{slash}TIM2_ETR{slash}SPI1_NSS{slash}SPI3_NSS{slash}I2S3_WS-Pad138)") (class "Default")
      (node (ref "U1") (pin "138") (pinfunction "PA15/JTDI/TIM2_CH1/TIM2_ETR/SPI1_NSS/SPI3_NSS/I2S3_WS_138") (pintype "passive+no_connect"))
    )
    (net (code "144") (name "unconnected-(U1-PB0{slash}TIM1_CH2N{slash}TIM3_CH3{slash}TIM8_CH2N{slash}LCD_R3{slash}OTG_HS_ULPI_D1{slash}ETH_MII_RXD2{slash}ADC12_IN8-Pad56)") (class "Default")
      (node (ref "U1") (pin "56") (pinfunction "PB0/TIM1_CH2N/TIM3_CH3/TIM8_CH2N/LCD_R3/OTG_HS_ULPI_D1/ETH_MII_RXD2/ADC12_IN8_56") (pintype "passive+no_connect"))
    )
    (net (code "145") (name "unconnected-(U1-PB1{slash}TIM1_CH3N{slash}TIM3_CH4{slash}TIM8_CH3N{slash}LCD_R6{slash}OTG_HS_ULPI_D2{slash}ETH_MII_RXD3{slash}ADC12_IN9-Pad57)") (class "Default")
      (node (ref "U1") (pin "57") (pinfunction "PB1/TIM1_CH3N/TIM3_CH4/TIM8_CH3N/LCD_R6/OTG_HS_ULPI_D2/ETH_MII_RXD3/ADC12_IN9_57") (pintype "passive+no_connect"))
    )
    (net (code "146") (name "unconnected-(U1-PB3{slash}JTDO{slash}TIM2_CH2{slash}SPI1_SCK{slash}SPI3_SCK{slash}I2S3_CK-Pad161)") (class "Default")
      (node (ref "U1") (pin "161") (pinfunction "PB3/JTDO/TIM2_CH2/SPI1_SCK/SPI3_SCK/I2S3_CK_161") (pintype "passive+no_connect"))
    )
    (net (code "147") (name "unconnected-(U1-PB4{slash}NJTRST{slash}TIM3_CH1{slash}SPI1_MISO{slash}SPI3_MISO{slash}I2S3ext_SD-Pad162)") (class "Default")
      (node (ref "U1") (pin "162") (pinfunction "PB4/NJTRST/TIM3_CH1/SPI1_MISO/SPI3_MISO/I2S3ext_SD_162") (pintype "passive+no_connect"))
    )
    (net (code "148") (name "unconnected-(U1-PB7{slash}TIM4_CH2{slash}I2C1_SDA{slash}U1_RX{slash}FMC_NL{slash}DCMI_VSYNC-Pad165)") (class "Default")
      (node (ref "U1") (pin "165") (pinfunction "PB7/TIM4_CH2/I2C1_SDA/U1_RX/FMC_NL/DCMI_VSYNC_165") (pintype "passive+no_connect"))
    )
    (net (code "149") (name "unconnected-(U1-PB10{slash}TIM2_CH3{slash}I2C2_SCL{slash}SPI2_SCK{slash}I2S2_CK{slash}U3_TX{slash}OTG_HS_ULPI_D3{slash}ETH_MII_RX_ER{slash}LCD_G4-Pad79)") (class "Default")
      (node (ref "U1") (pin "79") (pinfunction "PB10/TIM2_CH3/I2C2_SCL/SPI2_SCK/I2S2_CK/U3_TX/OTG_HS_ULPI_D3/ETH_MII_RX_ER/LCD_G4_79") (pintype "passive+no_connect"))
    )
    (net (code "150") (name "unconnected-(U1-PB11{slash}TIM2_CH4{slash}I2C2_SDA{slash}U3_RX{slash}OTG_HS_ULPI_D4{slash}ETH_MII_TX_EN{slash}ETH_RMII_TX_EN{slash}LCD_G5-Pad80)") (class "Default")
      (node (ref "U1") (pin "80") (pinfunction "PB11/TIM2_CH4/I2C2_SDA/U3_RX/OTG_HS_ULPI_D4/ETH_MII_TX_EN/ETH_RMII_TX_EN/LCD_G5_80") (pintype "passive+no_connect"))
    )
    (net (code "151") (name "unconnected-(U1-PC13{slash}TAMP_1-Pad8)") (class "Default")
      (node (ref "U1") (pin "8") (pinfunction "PC13/TAMP_1_8") (pintype "passive+no_connect"))
    )
    (net (code "152") (name "unconnected-(U1-PD3{slash}SPI2_SCK{slash}I2S2_CK{slash}U2_CTS{slash}FMC_CLK{slash}DCMI_D5{slash}LCD_G7-Pad145)") (class "Default")
      (node (ref "U1") (pin "145") (pinfunction "PD3/SPI2_SCK/I2S2_CK/U2_CTS/FMC_CLK/DCMI_D5/LCD_G7_145") (pintype "passive+no_connect"))
    )
    (net (code "153") (name "unconnected-(U1-PD4{slash}U2_RTS{slash}FMC_NOE-Pad146)") (class "Default")
      (node (ref "U1") (pin "146") (pinfunction "PD4/U2_RTS/FMC_NOE_146") (pintype "passive+no_connect"))
    )
    (net (code "154") (name "unconnected-(U1-PD5{slash}U2_TX{slash}FMC_NWE-Pad147)") (class "Default")
      (node (ref "U1") (pin "147") (pinfunction "PD5/U2_TX/FMC_NWE_147") (pintype "passive+no_connect"))
    )
    (net (code "155") (name "unconnected-(U1-PD7{slash}U2_CK{slash}FMC_NE1{slash}FMC_NCE2-Pad151)") (class "Default")
      (node (ref "U1") (pin "151") (pinfunction "PD7/U2_CK/FMC_NE1/FMC_NCE2_151") (pintype "passive+no_connect"))
    )
    (net (code "156") (name "unconnected-(U1-PD10{slash}U3_CK{slash}FMC_D15{slash}LCD_B3-Pad98)") (class "Default")
      (node (ref "U1") (pin "98") (pinfunction "PD10/U3_CK/FMC_D15/LCD_B3_98") (pintype "passive+no_connect"))
    )
    (net (code "157") (name "unconnected-(U1-PD11{slash}U3_CTS{slash}FMC_A16-Pad99)") (class "Default")
      (node (ref "U1") (pin "99") (pinfunction "PD11/U3_CTS/FMC_A16_99") (pintype "passive+no_connect"))
    )
    (net (code "158") (name "unconnected-(U1-PE3{slash}SAI1_SD_B{slash}FMC_A19-Pad2)") (class "Default")
      (node (ref "U1") (pin "2") (pinfunction "PE3/SAI1_SD_B/FMC_A19_2") (pintype "passive+no_connect"))
    )
    (net (code "159") (name "unconnected-(U1-PE10{slash}TIM1_CH2N{slash}FMC_D7-Pad73)") (class "Default")
      (node (ref "U1") (pin "73") (pinfunction "PE10/TIM1_CH2N/FMC_D7_73") (pintype "passive+no_connect"))
    )
    (net (code "160") (name "unconnected-(U1-PF5{slash}FMC_A5{slash}ADC3_IN15-Pad21)") (class "Default")
      (node (ref "U1") (pin "21") (pinfunction "PF5/FMC_A5/ADC3_IN15_21") (pintype "passive+no_connect"))
    )
    (net (code "161") (name "unconnected-(U1-PF10{slash}FMC_INTR{slash}DCMI_D11{slash}LCD_DE{slash}ADC3_IN8-Pad28)") (class "Default")
      (node (ref "U1") (pin "28") (pinfunction "PF10/FMC_INTR/DCMI_D11/LCD_DE/ADC3_IN8_28") (pintype "passive+no_connect"))
    )
    (net (code "162") (name "unconnected-(U1-PF11{slash}SPI5_MOSI{slash}FMC_SDNRAS{slash}DCMI_D12-Pad59)") (class "Default")
      (node (ref "U1") (pin "59") (pinfunction "PF11/SPI5_MOSI/FMC_SDNRAS/DCMI_D12_59") (pintype "passive+no_connect"))
    )
    (net (code "163") (name "unconnected-(U1-PF12{slash}FMC_A6-Pad60)") (class "Default")
      (node (ref "U1") (pin "60") (pinfunction "PF12/FMC_A6_60") (pintype "passive+no_connect"))
    )
    (net (code "164") (name "unconnected-(U1-PG9{slash}U6_RX{slash}FMC_NE2{slash}FMC_NCE3-Pad152)") (class "Default")
      (node (ref "U1") (pin "152") (pinfunction "PG9/U6_RX/FMC_NE2/FMC_NCE3_152") (pintype "passive+no_connect"))
    )
    (net (code "165") (name "unconnected-(U1-PG10{slash}LCD_G3{slash}FMC_NE3{slash}FMC_NCE4_1{slash}DCMI_D2{slash}LCD_B2-Pad153)") (class "Default")
      (node (ref "U1") (pin "153") (pinfunction "PG10/LCD_G3/FMC_NE3/FMC_NCE4_1/DCMI_D2/LCD_B2_153") (pintype "passive+no_connect"))
    )
    (net (code "166") (name "unconnected-(U1-PG11{slash}ETH_MII_TX_EN{slash}ETH_RMII_TX_EN{slash}FMC_NCE4_2{slash}DCMI_D3{slash}LCD_B3-Pad154)") (class "Default")
      (node (ref "U1") (pin "154") (pinfunction "PG11/ETH_MII_TX_EN/ETH_RMII_TX_EN/FMC_NCE4_2/DCMI_D3/LCD_B3_154") (pintype "passive+no_connect"))
    )
    (net (code "167") (name "unconnected-(U1-PG15{slash}U6_CTS{slash}FMC_SDNCAS{slash}DCMI_D13-Pad160)") (class "Default")
      (node (ref "U1") (pin "160") (pinfunction "PG15/U6_CTS/FMC_SDNCAS/DCMI_D13_160") (pintype "passive+no_connect"))
    )
    (net (code "168") (name "unconnected-(U1-PH2{slash}ETH_MII_CRS{slash}FMC_SDCKE0{slash}LCD_R0-Pad43)") (class "Default")
      (node (ref "U1") (pin "43") (pinfunction "PH2/ETH_MII_CRS/FMC_SDCKE0/LCD_R0_43") (pintype "passive+no_connect"))
    )
    (net (code "169") (name "unconnected-(U1-PH3{slash}ETH_MII_COL{slash}FMC_SDNE0{slash}LCD_R1-Pad44)") (class "Default")
      (node (ref "U1") (pin "44") (pinfunction "PH3/ETH_MII_COL/FMC_SDNE0/LCD_R1_44") (pintype "passive+no_connect"))
    )
    (net (code "170") (name "unconnected-(U1-PH9{slash}I2C3_SMBA{slash}TIM12_CH2{slash}FMC_D17{slash}DCMI_D0{slash}LCD_R3-Pad86)") (class "Default")
      (node (ref "U1") (pin "86") (pinfunction "PH9/I2C3_SMBA/TIM12_CH2/FMC_D17/DCMI_D0/LCD_R3_86") (pintype "passive+no_connect"))
    )
    (net (code "171") (name "unconnected-(U1-PH13{slash}TIM8_CH1N{slash}CAN1_TX{slash}FMC_D21{slash}LCD_G2-Pad128)") (class "Default")
      (node (ref "U1") (pin "128") (pinfunction "PH13/TIM8_CH1N/CAN1_TX/FMC_D21/LCD_G2_128") (pintype "passive+no_connect"))
    )
    (net (code "172") (name "unconnected-(U1-PH14{slash}TIM8_CH2N{slash}FMC_D22{slash}DCMI_D4{slash}LCD_G3-Pad129)") (class "Default")
      (node (ref "U1") (pin "129") (pinfunction "PH14/TIM8_CH2N/FMC_D22/DCMI_D4/LCD_G3_129") (pintype "passive+no_connect"))
    )
    (net (code "173") (name "unconnected-(U1-PH15{slash}TIM8_CH3N{slash}FMC_D23{slash}DCMI_D11{slash}LCD_G4-Pad130)") (class "Default")
      (node (ref "U1") (pin "130") (pinfunction "PH15/TIM8_CH3N/FMC_D23/DCMI_D11/LCD_G4_130") (pintype "passive+no_connect"))
    )
    (net (code "174") (name "unconnected-(U1-PI1{slash}SPI2_SCK{slash}I2S2_CK{slash}FMC_D25{slash}DCMI_D8{slash}LCD_G6-Pad132)") (class "Default")
      (node (ref "U1") (pin "132") (pinfunction "PI1/SPI2_SCK/I2S2_CK/FMC_D25/DCMI_D8/LCD_G6_132") (pintype "passive+no_connect"))
    )
    (net (code "175") (name "unconnected-(U1-PI3{slash}TIM8_ETR{slash}SPI2_MOSI{slash}I2S2_SD{slash}FMC_D27{slash}DCMI_D10-Pad134)") (class "Default")
      (node (ref "U1") (pin "134") (pinfunction "PI3/TIM8_ETR/SPI2_MOSI/I2S2_SD/FMC_D27/DCMI_D10_134") (pintype "passive+no_connect"))
    )
    (net (code "176") (name "unconnected-(U1-PI4{slash}TIM8_BKIN{slash}FMC_NBL2{slash}DCMI_D5{slash}LCD_B4-Pad173)") (class "Default")
      (node (ref "U1") (pin "173") (pinfunction "PI4/TIM8_BKIN/FMC_NBL2/DCMI_D5/LCD_B4_173") (pintype "passive+no_connect"))
    )
    (net (code "177") (name "unconnected-(U1-PI8{slash}TAMP_2-Pad7)") (class "Default")
      (node (ref "U1") (pin "7") (pinfunction "PI8/TAMP_2_7") (pintype "passive+no_connect"))
    )
    (net (code "178") (name "unconnected-(U1-PI9{slash}CAN1_RX{slash}FMC_D30{slash}LCD_VSYNC-Pad11)") (class "Default")
      (node (ref "U1") (pin "11") (pinfunction "PI9/CAN1_RX/FMC_D30/LCD_VSYNC_11") (pintype "passive+no_connect"))
    )
    (net (code "179") (name "unconnected-(U1-PI10{slash}ETH_MII_RX_ER{slash}FMC_D31{slash}LCD_HSYNC-Pad12)") (class "Default")
      (node (ref "U1") (pin "12") (pinfunction "PI10/ETH_MII_RX_ER/FMC_D31/LCD_HSYNC_12") (pintype "passive+no_connect"))
    )
    (net (code "180") (name "unconnected-(U1-PI11{slash}OTG_HS_ULPI_DIR-Pad13)") (class "Default")
      (node (ref "U1") (pin "13") (pinfunction "PI11/OTG_HS_ULPI_DIR_13") (pintype "passive+no_connect"))
    )
    (net (code "181") (name "unconnected-(USB-ID-Pad4)") (class "Default")
      (node (ref "USB") (pin "4") (pinfunction "ID_4") (pintype "passive+no_connect"))
    )
    (net (code "182") (name "unconnected-(USB-SLD-PadS1_S2_S3_S4_S5_S6)") (class "Default")
      (node (ref "USB") (pin "S1_S2_S3_S4_S5_S6") (pinfunction "SLD_S1_S2_S3_S4_S5_S6") (pintype "passive"))
    )
  )
)
